# shield.net
KiCad netlist of a schematic drawn in EAGLE
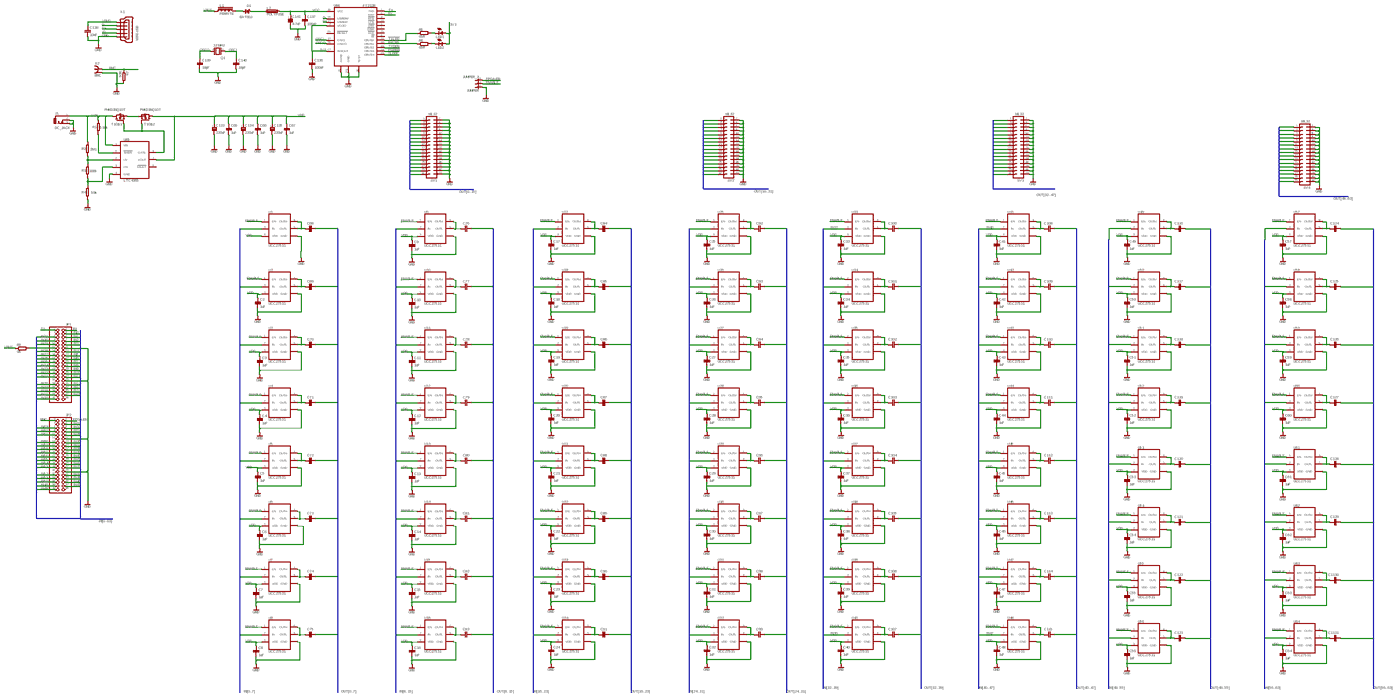
[diagram p0: schematic, sheet 1, overview]
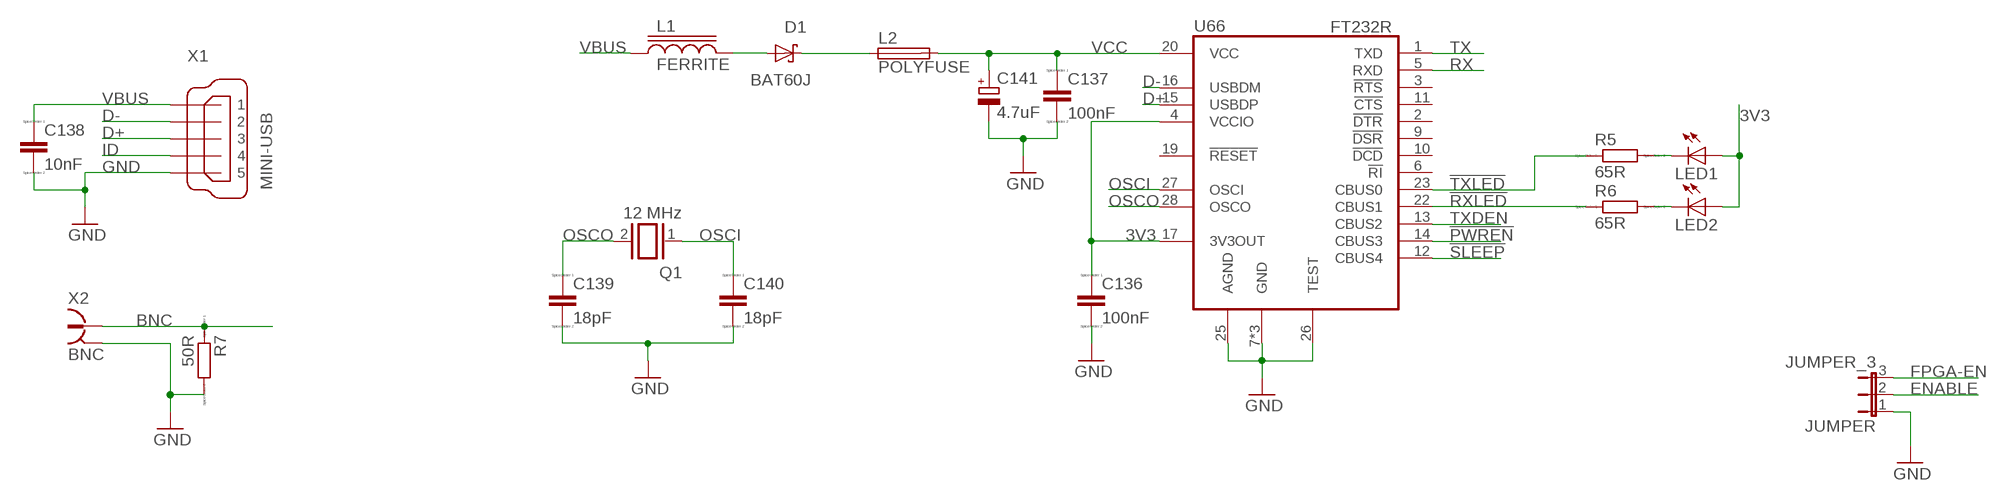
[diagram p1: schematic, sheet 1, part 1 of 4]
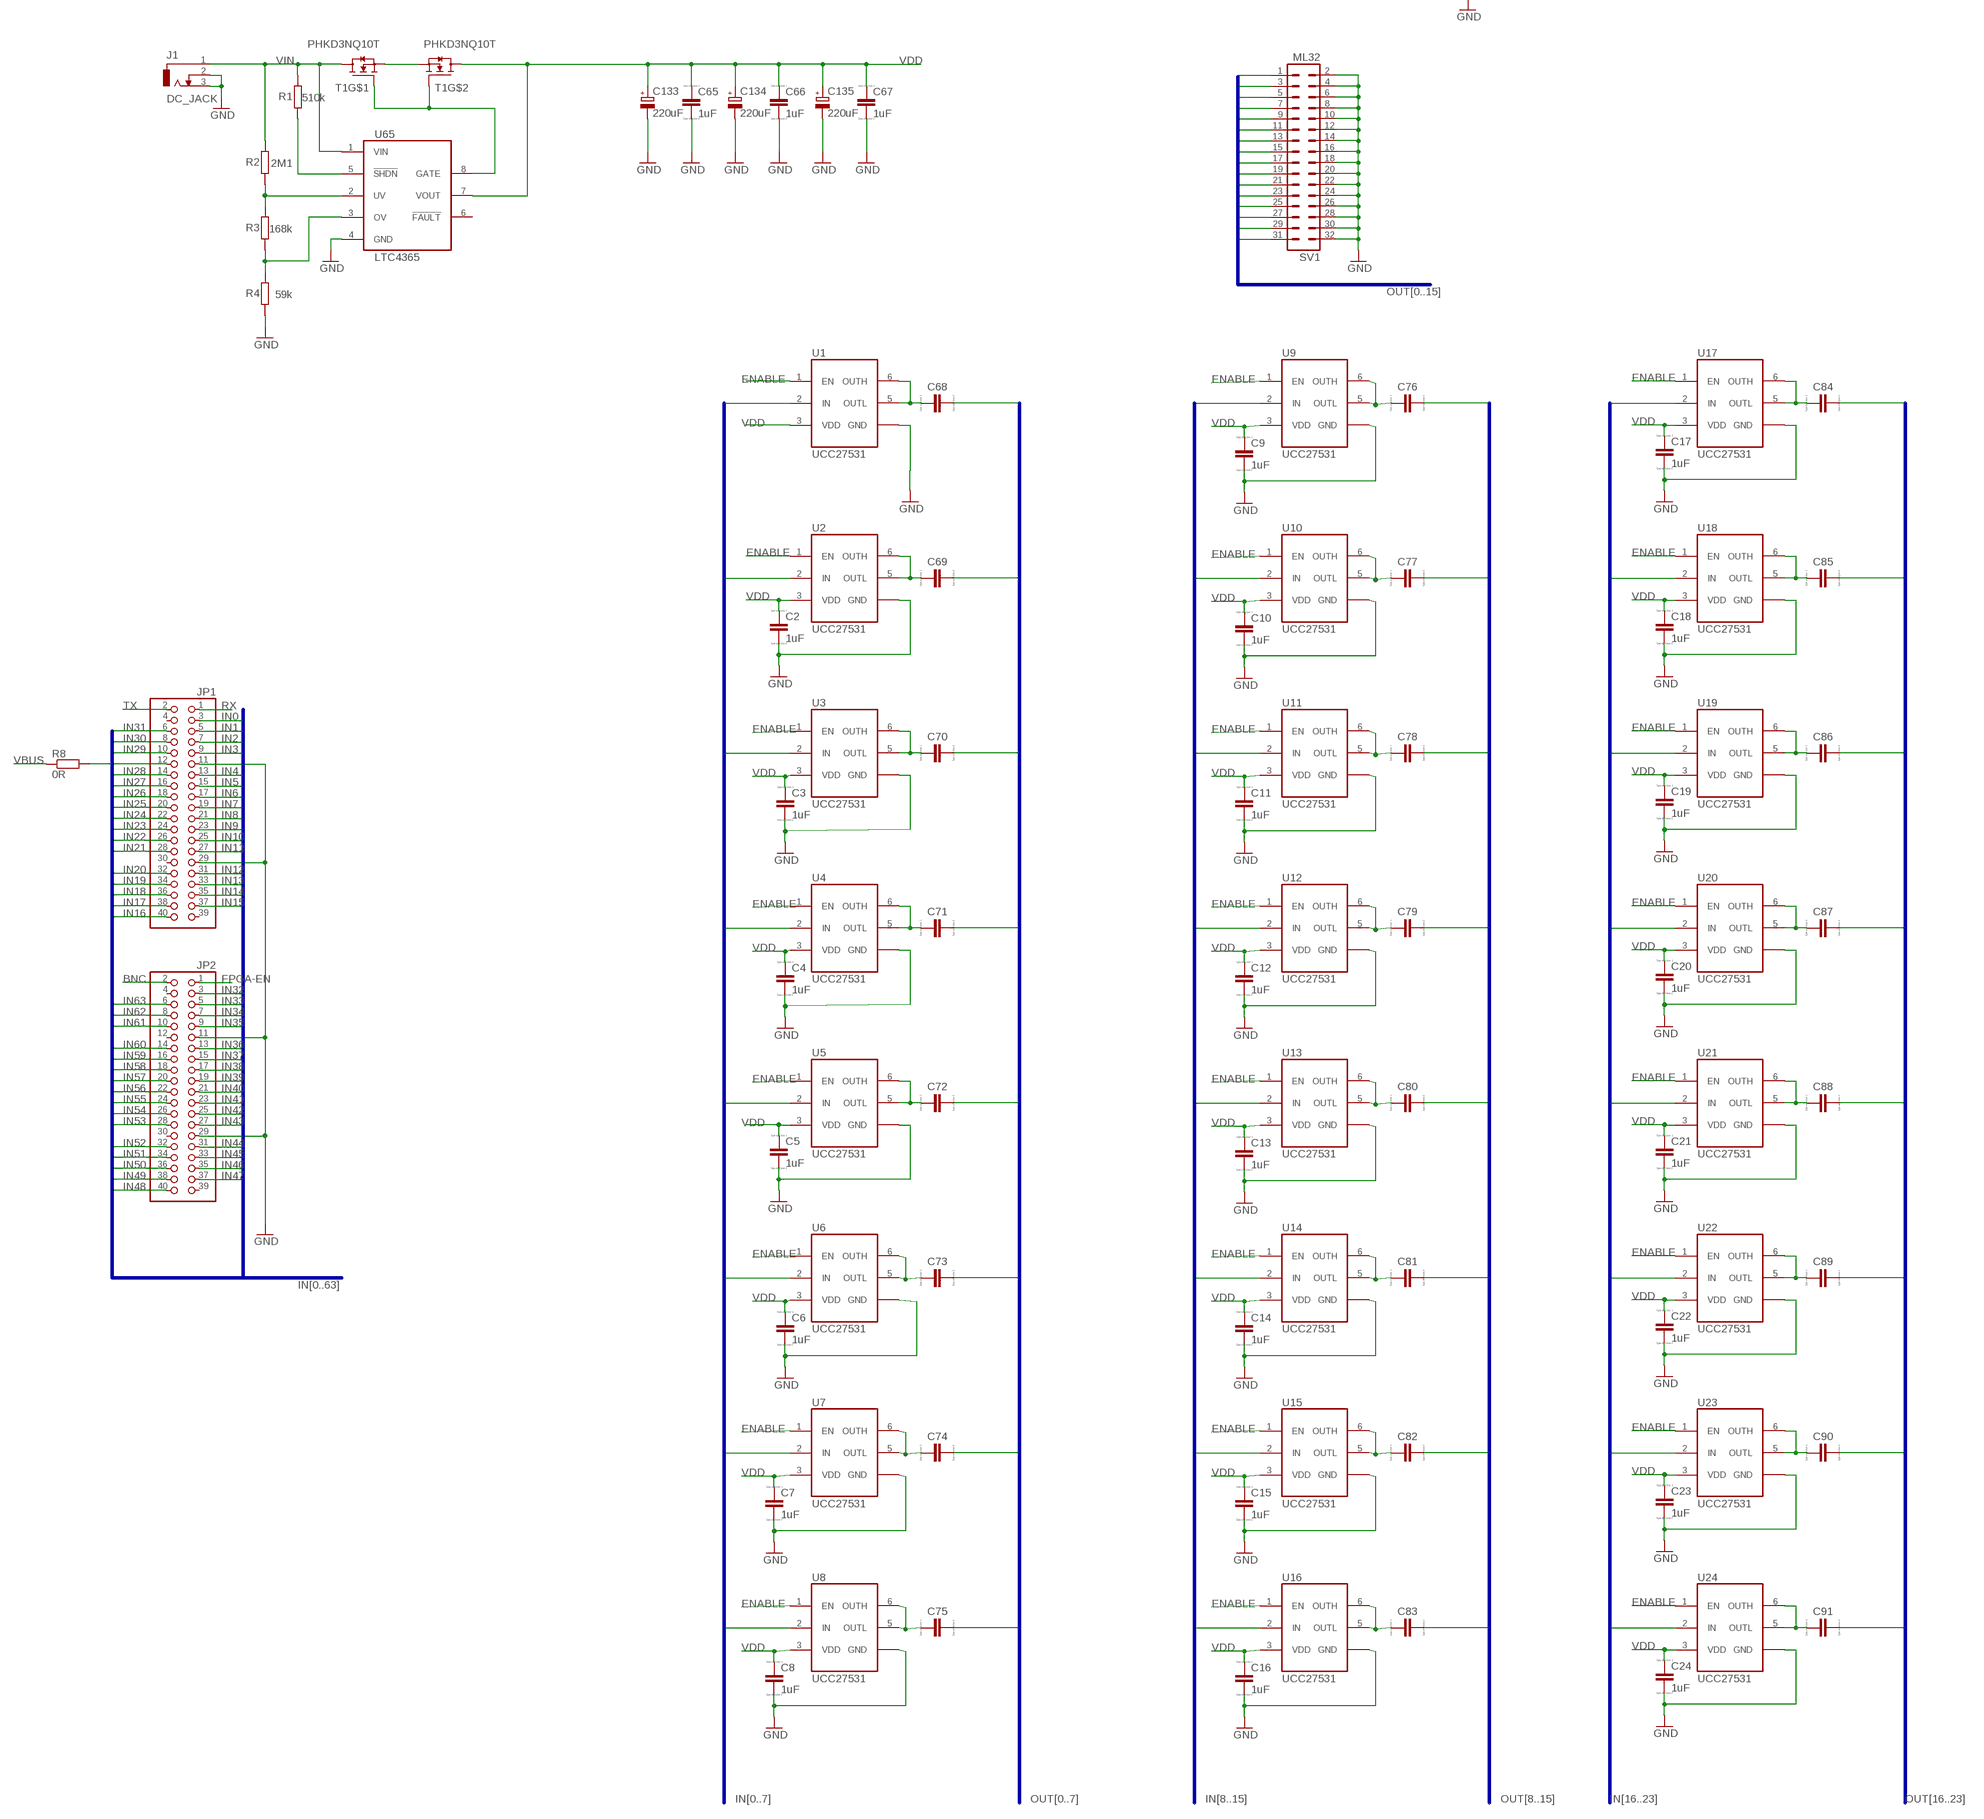
[diagram p2: schematic, sheet 1, part 2 of 4]
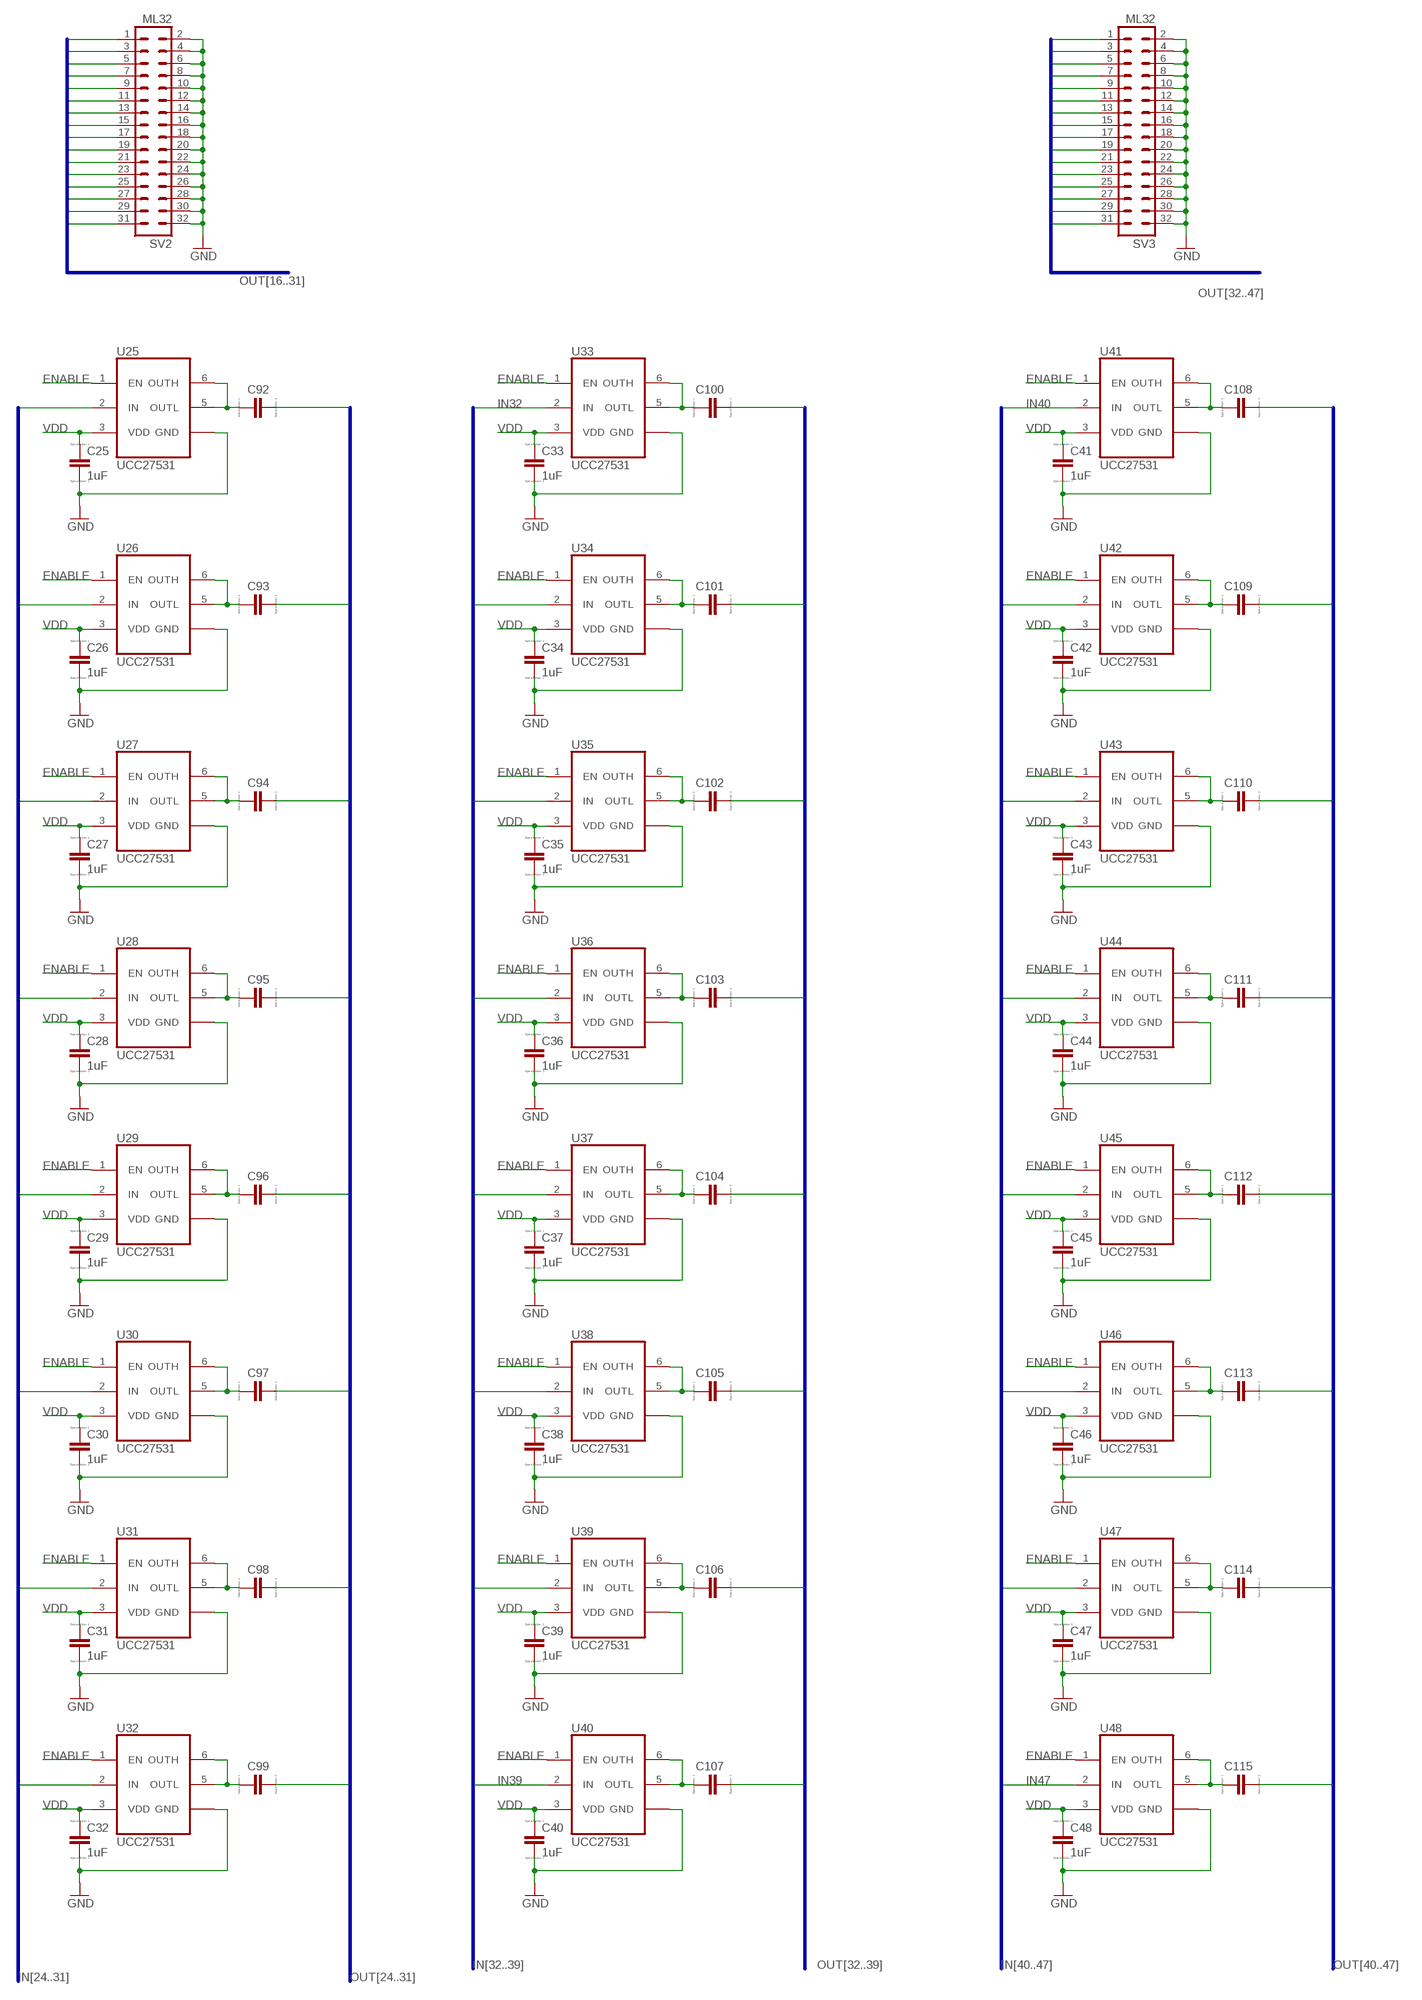
[diagram p3: schematic, sheet 1, part 3 of 4]
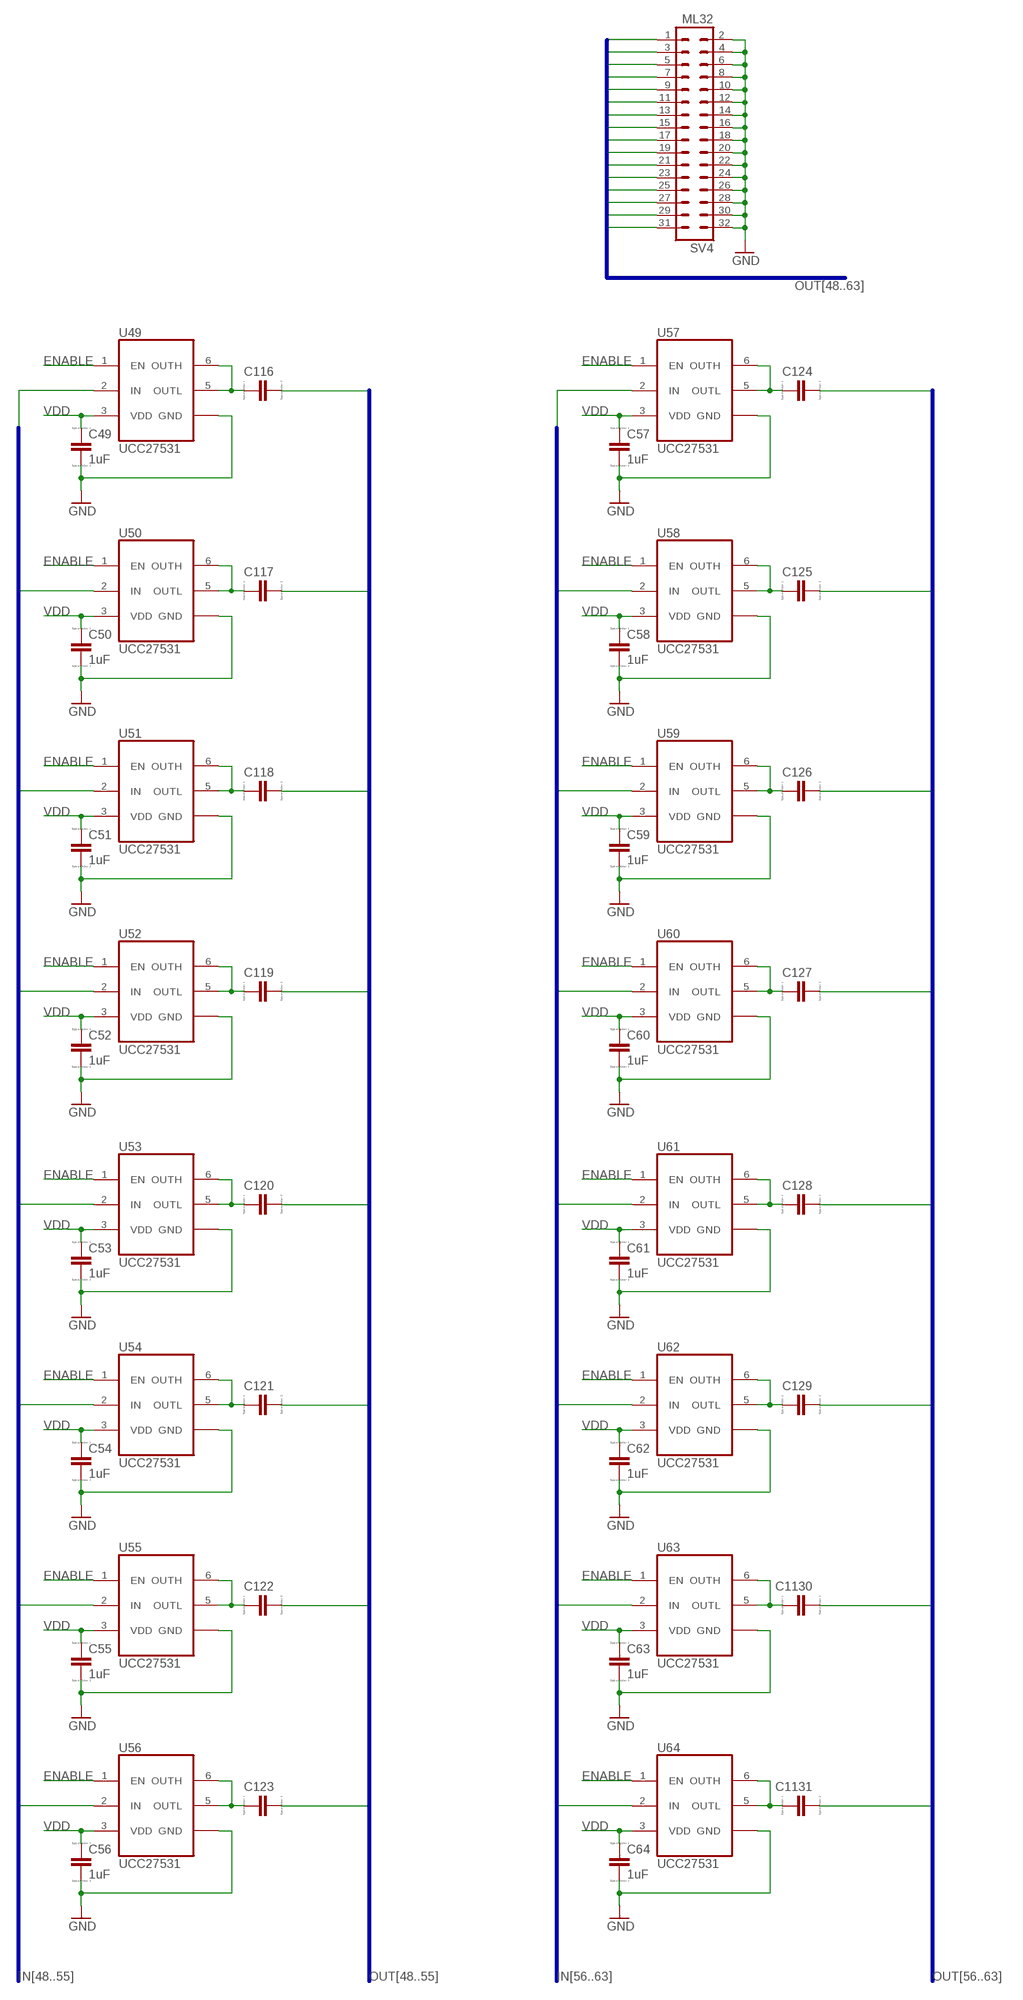
[diagram p4: schematic, sheet 1, part 4 of 4]

(export (version "E")
  (design (tool "Eeschema 10.0.6"))
  (components
    (comp (ref "C2")
      (value "1uF")
      (footprint "eagle-import:C0805")
      (libsource (lib "eagle-import") (part "C"))
    )
    (comp (ref "C3")
      (value "1uF")
      (footprint "eagle-import:C0805")
      (libsource (lib "eagle-import") (part "C"))
    )
    (comp (ref "C4")
      (value "1uF")
      (footprint "eagle-import:C0805")
      (libsource (lib "eagle-import") (part "C"))
    )
    (comp (ref "C5")
      (value "1uF")
      (footprint "eagle-import:C0805")
      (libsource (lib "eagle-import") (part "C"))
    )
    (comp (ref "C6")
      (value "1uF")
      (footprint "eagle-import:C0805")
      (libsource (lib "eagle-import") (part "C"))
    )
    (comp (ref "C7")
      (value "1uF")
      (footprint "eagle-import:C0805")
      (libsource (lib "eagle-import") (part "C"))
    )
    (comp (ref "C8")
      (value "1uF")
      (footprint "eagle-import:C0805")
      (libsource (lib "eagle-import") (part "C"))
    )
    (comp (ref "C9")
      (value "1uF")
      (footprint "eagle-import:C0805")
      (libsource (lib "eagle-import") (part "C"))
    )
    (comp (ref "C10")
      (value "1uF")
      (footprint "eagle-import:C0805")
      (libsource (lib "eagle-import") (part "C"))
    )
    (comp (ref "C11")
      (value "1uF")
      (footprint "eagle-import:C0805")
      (libsource (lib "eagle-import") (part "C"))
    )
    (comp (ref "C12")
      (value "1uF")
      (footprint "eagle-import:C0805")
      (libsource (lib "eagle-import") (part "C"))
    )
    (comp (ref "C13")
      (value "1uF")
      (footprint "eagle-import:C0805")
      (libsource (lib "eagle-import") (part "C"))
    )
    (comp (ref "C14")
      (value "1uF")
      (footprint "eagle-import:C0805")
      (libsource (lib "eagle-import") (part "C"))
    )
    (comp (ref "C15")
      (value "1uF")
      (footprint "eagle-import:C0805")
      (libsource (lib "eagle-import") (part "C"))
    )
    (comp (ref "C16")
      (value "1uF")
      (footprint "eagle-import:C0805")
      (libsource (lib "eagle-import") (part "C"))
    )
    (comp (ref "C17")
      (value "1uF")
      (footprint "eagle-import:C0805")
      (libsource (lib "eagle-import") (part "C"))
    )
    (comp (ref "C18")
      (value "1uF")
      (footprint "eagle-import:C0805")
      (libsource (lib "eagle-import") (part "C"))
    )
    (comp (ref "C19")
      (value "1uF")
      (footprint "eagle-import:C0805")
      (libsource (lib "eagle-import") (part "C"))
    )
    (comp (ref "C20")
      (value "1uF")
      (footprint "eagle-import:C0805")
      (libsource (lib "eagle-import") (part "C"))
    )
    (comp (ref "C21")
      (value "1uF")
      (footprint "eagle-import:C0805")
      (libsource (lib "eagle-import") (part "C"))
    )
    (comp (ref "C22")
      (value "1uF")
      (footprint "eagle-import:C0805")
      (libsource (lib "eagle-import") (part "C"))
    )
    (comp (ref "C23")
      (value "1uF")
      (footprint "eagle-import:C0805")
      (libsource (lib "eagle-import") (part "C"))
    )
    (comp (ref "C24")
      (value "1uF")
      (footprint "eagle-import:C0805")
      (libsource (lib "eagle-import") (part "C"))
    )
    (comp (ref "C25")
      (value "1uF")
      (footprint "eagle-import:C0805")
      (libsource (lib "eagle-import") (part "C"))
    )
    (comp (ref "C26")
      (value "1uF")
      (footprint "eagle-import:C0805")
      (libsource (lib "eagle-import") (part "C"))
    )
    (comp (ref "C27")
      (value "1uF")
      (footprint "eagle-import:C0805")
      (libsource (lib "eagle-import") (part "C"))
    )
    (comp (ref "C28")
      (value "1uF")
      (footprint "eagle-import:C0805")
      (libsource (lib "eagle-import") (part "C"))
    )
    (comp (ref "C29")
      (value "1uF")
      (footprint "eagle-import:C0805")
      (libsource (lib "eagle-import") (part "C"))
    )
    (comp (ref "C30")
      (value "1uF")
      (footprint "eagle-import:C0805")
      (libsource (lib "eagle-import") (part "C"))
    )
    (comp (ref "C31")
      (value "1uF")
      (footprint "eagle-import:C0805")
      (libsource (lib "eagle-import") (part "C"))
    )
    (comp (ref "C32")
      (value "1uF")
      (footprint "eagle-import:C0805")
      (libsource (lib "eagle-import") (part "C"))
    )
    (comp (ref "C33")
      (value "1uF")
      (footprint "eagle-import:C0805")
      (libsource (lib "eagle-import") (part "C"))
    )
    (comp (ref "C34")
      (value "1uF")
      (footprint "eagle-import:C0805")
      (libsource (lib "eagle-import") (part "C"))
    )
    (comp (ref "C35")
      (value "1uF")
      (footprint "eagle-import:C0805")
      (libsource (lib "eagle-import") (part "C"))
    )
    (comp (ref "C36")
      (value "1uF")
      (footprint "eagle-import:C0805")
      (libsource (lib "eagle-import") (part "C"))
    )
    (comp (ref "C37")
      (value "1uF")
      (footprint "eagle-import:C0805")
      (libsource (lib "eagle-import") (part "C"))
    )
    (comp (ref "C38")
      (value "1uF")
      (footprint "eagle-import:C0805")
      (libsource (lib "eagle-import") (part "C"))
    )
    (comp (ref "C39")
      (value "1uF")
      (footprint "eagle-import:C0805")
      (libsource (lib "eagle-import") (part "C"))
    )
    (comp (ref "C40")
      (value "1uF")
      (footprint "eagle-import:C0805")
      (libsource (lib "eagle-import") (part "C"))
    )
    (comp (ref "C41")
      (value "1uF")
      (footprint "eagle-import:C0805")
      (libsource (lib "eagle-import") (part "C"))
    )
    (comp (ref "C42")
      (value "1uF")
      (footprint "eagle-import:C0805")
      (libsource (lib "eagle-import") (part "C"))
    )
    (comp (ref "C43")
      (value "1uF")
      (footprint "eagle-import:C0805")
      (libsource (lib "eagle-import") (part "C"))
    )
    (comp (ref "C44")
      (value "1uF")
      (footprint "eagle-import:C0805")
      (libsource (lib "eagle-import") (part "C"))
    )
    (comp (ref "C45")
      (value "1uF")
      (footprint "eagle-import:C0805")
      (libsource (lib "eagle-import") (part "C"))
    )
    (comp (ref "C46")
      (value "1uF")
      (footprint "eagle-import:C0805")
      (libsource (lib "eagle-import") (part "C"))
    )
    (comp (ref "C47")
      (value "1uF")
      (footprint "eagle-import:C0805")
      (libsource (lib "eagle-import") (part "C"))
    )
    (comp (ref "C48")
      (value "1uF")
      (footprint "eagle-import:C0805")
      (libsource (lib "eagle-import") (part "C"))
    )
    (comp (ref "C49")
      (value "1uF")
      (footprint "eagle-import:C0805")
      (libsource (lib "eagle-import") (part "C"))
    )
    (comp (ref "C50")
      (value "1uF")
      (footprint "eagle-import:C0805")
      (libsource (lib "eagle-import") (part "C"))
    )
    (comp (ref "C51")
      (value "1uF")
      (footprint "eagle-import:C0805")
      (libsource (lib "eagle-import") (part "C"))
    )
    (comp (ref "C52")
      (value "1uF")
      (footprint "eagle-import:C0805")
      (libsource (lib "eagle-import") (part "C"))
    )
    (comp (ref "C53")
      (value "1uF")
      (footprint "eagle-import:C0805")
      (libsource (lib "eagle-import") (part "C"))
    )
    (comp (ref "C54")
      (value "1uF")
      (footprint "eagle-import:C0805")
      (libsource (lib "eagle-import") (part "C"))
    )
    (comp (ref "C55")
      (value "1uF")
      (footprint "eagle-import:C0805")
      (libsource (lib "eagle-import") (part "C"))
    )
    (comp (ref "C56")
      (value "1uF")
      (footprint "eagle-import:C0805")
      (libsource (lib "eagle-import") (part "C"))
    )
    (comp (ref "C57")
      (value "1uF")
      (footprint "eagle-import:C0805")
      (libsource (lib "eagle-import") (part "C"))
    )
    (comp (ref "C58")
      (value "1uF")
      (footprint "eagle-import:C0805")
      (libsource (lib "eagle-import") (part "C"))
    )
    (comp (ref "C59")
      (value "1uF")
      (footprint "eagle-import:C0805")
      (libsource (lib "eagle-import") (part "C"))
    )
    (comp (ref "C60")
      (value "1uF")
      (footprint "eagle-import:C0805")
      (libsource (lib "eagle-import") (part "C"))
    )
    (comp (ref "C61")
      (value "1uF")
      (footprint "eagle-import:C0805")
      (libsource (lib "eagle-import") (part "C"))
    )
    (comp (ref "C62")
      (value "1uF")
      (footprint "eagle-import:C0805")
      (libsource (lib "eagle-import") (part "C"))
    )
    (comp (ref "C63")
      (value "1uF")
      (footprint "eagle-import:C0805")
      (libsource (lib "eagle-import") (part "C"))
    )
    (comp (ref "C64")
      (value "1uF")
      (footprint "eagle-import:C0805")
      (libsource (lib "eagle-import") (part "C"))
    )
    (comp (ref "C65")
      (value "1uF")
      (footprint "eagle-import:C0805")
      (libsource (lib "eagle-import") (part "C"))
    )
    (comp (ref "C66")
      (value "1uF")
      (footprint "eagle-import:C0805")
      (libsource (lib "eagle-import") (part "C"))
    )
    (comp (ref "C67")
      (value "1uF")
      (footprint "eagle-import:C0805")
      (libsource (lib "eagle-import") (part "C"))
    )
    (comp (ref "C68")
      (value "C")
      (footprint "eagle-import:C0805")
      (libsource (lib "eagle-import") (part "C"))
    )
    (comp (ref "C69")
      (value "C")
      (footprint "eagle-import:C0805")
      (libsource (lib "eagle-import") (part "C"))
    )
    (comp (ref "C70")
      (value "C")
      (footprint "eagle-import:C0805")
      (libsource (lib "eagle-import") (part "C"))
    )
    (comp (ref "C71")
      (value "C")
      (footprint "eagle-import:C0805")
      (libsource (lib "eagle-import") (part "C"))
    )
    (comp (ref "C72")
      (value "C")
      (footprint "eagle-import:C0805")
      (libsource (lib "eagle-import") (part "C"))
    )
    (comp (ref "C73")
      (value "C")
      (footprint "eagle-import:C0805")
      (libsource (lib "eagle-import") (part "C"))
    )
    (comp (ref "C74")
      (value "C")
      (footprint "eagle-import:C0805")
      (libsource (lib "eagle-import") (part "C"))
    )
    (comp (ref "C75")
      (value "C")
      (footprint "eagle-import:C0805")
      (libsource (lib "eagle-import") (part "C"))
    )
    (comp (ref "C76")
      (value "C")
      (footprint "eagle-import:C0805")
      (libsource (lib "eagle-import") (part "C"))
    )
    (comp (ref "C77")
      (value "C")
      (footprint "eagle-import:C0805")
      (libsource (lib "eagle-import") (part "C"))
    )
    (comp (ref "C78")
      (value "C")
      (footprint "eagle-import:C0805")
      (libsource (lib "eagle-import") (part "C"))
    )
    (comp (ref "C79")
      (value "C")
      (footprint "eagle-import:C0805")
      (libsource (lib "eagle-import") (part "C"))
    )
    (comp (ref "C80")
      (value "C")
      (footprint "eagle-import:C0805")
      (libsource (lib "eagle-import") (part "C"))
    )
    (comp (ref "C81")
      (value "C")
      (footprint "eagle-import:C0805")
      (libsource (lib "eagle-import") (part "C"))
    )
    (comp (ref "C82")
      (value "C")
      (footprint "eagle-import:C0805")
      (libsource (lib "eagle-import") (part "C"))
    )
    (comp (ref "C83")
      (value "C")
      (footprint "eagle-import:C0805")
      (libsource (lib "eagle-import") (part "C"))
    )
    (comp (ref "C84")
      (value "C")
      (footprint "eagle-import:C0805")
      (libsource (lib "eagle-import") (part "C"))
    )
    (comp (ref "C85")
      (value "C")
      (footprint "eagle-import:C0805")
      (libsource (lib "eagle-import") (part "C"))
    )
    (comp (ref "C86")
      (value "C")
      (footprint "eagle-import:C0805")
      (libsource (lib "eagle-import") (part "C"))
    )
    (comp (ref "C87")
      (value "C")
      (footprint "eagle-import:C0805")
      (libsource (lib "eagle-import") (part "C"))
    )
    (comp (ref "C88")
      (value "C")
      (footprint "eagle-import:C0805")
      (libsource (lib "eagle-import") (part "C"))
    )
    (comp (ref "C89")
      (value "C")
      (footprint "eagle-import:C0805")
      (libsource (lib "eagle-import") (part "C"))
    )
    (comp (ref "C90")
      (value "C")
      (footprint "eagle-import:C0805")
      (libsource (lib "eagle-import") (part "C"))
    )
    (comp (ref "C91")
      (value "C")
      (footprint "eagle-import:C0805")
      (libsource (lib "eagle-import") (part "C"))
    )
    (comp (ref "C92")
      (value "C")
      (footprint "eagle-import:C0805")
      (libsource (lib "eagle-import") (part "C"))
    )
    (comp (ref "C93")
      (value "C")
      (footprint "eagle-import:C0805")
      (libsource (lib "eagle-import") (part "C"))
    )
    (comp (ref "C94")
      (value "C")
      (footprint "eagle-import:C0805")
      (libsource (lib "eagle-import") (part "C"))
    )
    (comp (ref "C95")
      (value "C")
      (footprint "eagle-import:C0805")
      (libsource (lib "eagle-import") (part "C"))
    )
    (comp (ref "C96")
      (value "C")
      (footprint "eagle-import:C0805")
      (libsource (lib "eagle-import") (part "C"))
    )
    (comp (ref "C97")
      (value "C")
      (footprint "eagle-import:C0805")
      (libsource (lib "eagle-import") (part "C"))
    )
    (comp (ref "C98")
      (value "C")
      (footprint "eagle-import:C0805")
      (libsource (lib "eagle-import") (part "C"))
    )
    (comp (ref "C99")
      (value "C")
      (footprint "eagle-import:C0805")
      (libsource (lib "eagle-import") (part "C"))
    )
    (comp (ref "C100")
      (value "C")
      (footprint "eagle-import:C0805")
      (libsource (lib "eagle-import") (part "C"))
    )
    (comp (ref "C101")
      (value "C")
      (footprint "eagle-import:C0805")
      (libsource (lib "eagle-import") (part "C"))
    )
    (comp (ref "C102")
      (value "C")
      (footprint "eagle-import:C0805")
      (libsource (lib "eagle-import") (part "C"))
    )
    (comp (ref "C103")
      (value "C")
      (footprint "eagle-import:C0805")
      (libsource (lib "eagle-import") (part "C"))
    )
    (comp (ref "C104")
      (value "C")
      (footprint "eagle-import:C0805")
      (libsource (lib "eagle-import") (part "C"))
    )
    (comp (ref "C105")
      (value "C")
      (footprint "eagle-import:C0805")
      (libsource (lib "eagle-import") (part "C"))
    )
    (comp (ref "C106")
      (value "C")
      (footprint "eagle-import:C0805")
      (libsource (lib "eagle-import") (part "C"))
    )
    (comp (ref "C107")
      (value "C")
      (footprint "eagle-import:C0805")
      (libsource (lib "eagle-import") (part "C"))
    )
    (comp (ref "C108")
      (value "C")
      (footprint "eagle-import:C0805")
      (libsource (lib "eagle-import") (part "C"))
    )
    (comp (ref "C109")
      (value "C")
      (footprint "eagle-import:C0805")
      (libsource (lib "eagle-import") (part "C"))
    )
    (comp (ref "C110")
      (value "C")
      (footprint "eagle-import:C0805")
      (libsource (lib "eagle-import") (part "C"))
    )
    (comp (ref "C111")
      (value "C")
      (footprint "eagle-import:C0805")
      (libsource (lib "eagle-import") (part "C"))
    )
    (comp (ref "C112")
      (value "C")
      (footprint "eagle-import:C0805")
      (libsource (lib "eagle-import") (part "C"))
    )
    (comp (ref "C113")
      (value "C")
      (footprint "eagle-import:C0805")
      (libsource (lib "eagle-import") (part "C"))
    )
    (comp (ref "C114")
      (value "C")
      (footprint "eagle-import:C0805")
      (libsource (lib "eagle-import") (part "C"))
    )
    (comp (ref "C115")
      (value "C")
      (footprint "eagle-import:C0805")
      (libsource (lib "eagle-import") (part "C"))
    )
    (comp (ref "C116")
      (value "C")
      (footprint "eagle-import:C0805")
      (libsource (lib "eagle-import") (part "C"))
    )
    (comp (ref "C117")
      (value "C")
      (footprint "eagle-import:C0805")
      (libsource (lib "eagle-import") (part "C"))
    )
    (comp (ref "C118")
      (value "C")
      (footprint "eagle-import:C0805")
      (libsource (lib "eagle-import") (part "C"))
    )
    (comp (ref "C119")
      (value "C")
      (footprint "eagle-import:C0805")
      (libsource (lib "eagle-import") (part "C"))
    )
    (comp (ref "C120")
      (value "C")
      (footprint "eagle-import:C0805")
      (libsource (lib "eagle-import") (part "C"))
    )
    (comp (ref "C121")
      (value "C")
      (footprint "eagle-import:C0805")
      (libsource (lib "eagle-import") (part "C"))
    )
    (comp (ref "C122")
      (value "C")
      (footprint "eagle-import:C0805")
      (libsource (lib "eagle-import") (part "C"))
    )
    (comp (ref "C123")
      (value "C")
      (footprint "eagle-import:C0805")
      (libsource (lib "eagle-import") (part "C"))
    )
    (comp (ref "C124")
      (value "C")
      (footprint "eagle-import:C0805")
      (libsource (lib "eagle-import") (part "C"))
    )
    (comp (ref "C125")
      (value "C")
      (footprint "eagle-import:C0805")
      (libsource (lib "eagle-import") (part "C"))
    )
    (comp (ref "C126")
      (value "C")
      (footprint "eagle-import:C0805")
      (libsource (lib "eagle-import") (part "C"))
    )
    (comp (ref "C127")
      (value "C")
      (footprint "eagle-import:C0805")
      (libsource (lib "eagle-import") (part "C"))
    )
    (comp (ref "C128")
      (value "C")
      (footprint "eagle-import:C0805")
      (libsource (lib "eagle-import") (part "C"))
    )
    (comp (ref "C129")
      (value "C")
      (footprint "eagle-import:C0805")
      (libsource (lib "eagle-import") (part "C"))
    )
    (comp (ref "C133")
      (value "220uF")
      (footprint "eagle-import:E5-10,5")
      (libsource (lib "eagle-import") (part "CPOL-EUE5-10.5"))
    )
    (comp (ref "C134")
      (value "220uF")
      (footprint "eagle-import:E5-10,5")
      (libsource (lib "eagle-import") (part "CPOL-EUE5-10.5"))
    )
    (comp (ref "C135")
      (value "220uF")
      (footprint "eagle-import:E5-10,5")
      (libsource (lib "eagle-import") (part "CPOL-EUE5-10.5"))
    )
    (comp (ref "C136")
      (value "100nF")
      (footprint "eagle-import:C0805")
      (libsource (lib "eagle-import") (part "C"))
    )
    (comp (ref "C137")
      (value "100nF")
      (footprint "eagle-import:C0805")
      (libsource (lib "eagle-import") (part "C"))
    )
    (comp (ref "C138")
      (value "10nF")
      (footprint "eagle-import:C0805")
      (libsource (lib "eagle-import") (part "C"))
    )
    (comp (ref "C139")
      (value "18pF")
      (footprint "eagle-import:C0603")
      (libsource (lib "eagle-import") (part "CC0603"))
    )
    (comp (ref "C140")
      (value "18pF")
      (footprint "eagle-import:C0603")
      (libsource (lib "eagle-import") (part "CC0603"))
    )
    (comp (ref "C141")
      (value "4.7uF")
      (footprint "eagle-import:E2-5")
      (libsource (lib "eagle-import") (part "CPOL-EUE2-5"))
    )
    (comp (ref "C1130")
      (value "C")
      (footprint "eagle-import:C0805")
      (libsource (lib "eagle-import") (part "C"))
    )
    (comp (ref "C1131")
      (value "C")
      (footprint "eagle-import:C0805")
      (libsource (lib "eagle-import") (part "C"))
    )
    (comp (ref "D1")
      (value "BAT60J")
      (footprint "eagle-import:SOD323_ST")
      (libsource (lib "eagle-import") (part "BAT60J"))
    )
    (comp (ref "J1")
      (value "DC_JACK")
      (footprint "eagle-import:DCJ0202")
      (libsource (lib "eagle-import") (part "DC_JACK"))
    )
    (comp (ref "JP1")
      (value "PINHD-2X20")
      (footprint "eagle-import:2X20")
      (libsource (lib "eagle-import") (part "PINHD-2X20"))
    )
    (comp (ref "JP2")
      (value "PINHD-2X20")
      (footprint "eagle-import:2X20")
      (libsource (lib "eagle-import") (part "PINHD-2X20"))
    )
    (comp (ref "JUMPER")
      (value "JUMPER_3")
      (footprint "eagle-import:JP2")
      (libsource (lib "eagle-import") (part "JUMPER_3"))
    )
    (comp (ref "L1")
      (value "FERRITE")
      (footprint "eagle-import:SML0805")
      (libsource (lib "eagle-import") (part "FERRITE"))
    )
    (comp (ref "L2")
      (value "POLYFUSE")
      (footprint "eagle-import:SML0805")
      (libsource (lib "eagle-import") (part "POLYFUSE"))
    )
    (comp (ref "LED1")
      (value "LEDSML1206")
      (footprint "eagle-import:SML1206")
      (libsource (lib "eagle-import") (part "LEDSML1206"))
    )
    (comp (ref "LED2")
      (value "LEDSML1206")
      (footprint "eagle-import:SML1206")
      (libsource (lib "eagle-import") (part "LEDSML1206"))
    )
    (comp (ref "Q1")
      (value "12 MHz")
      (footprint "eagle-import:QS")
      (libsource (lib "eagle-import") (part "XTAL/S"))
    )
    (comp (ref "R1")
      (value "510k")
      (footprint "eagle-import:R0805")
      (libsource (lib "eagle-import") (part "resistor_348_R-EU_R0805"))
    )
    (comp (ref "R2")
      (value "2M1")
      (footprint "eagle-import:R0805")
      (libsource (lib "eagle-import") (part "resistor_348_R-EU_R0805"))
    )
    (comp (ref "R3")
      (value "168k")
      (footprint "eagle-import:R0805")
      (libsource (lib "eagle-import") (part "resistor_348_R-EU_R0805"))
    )
    (comp (ref "R4")
      (value "59k")
      (footprint "eagle-import:R0805")
      (libsource (lib "eagle-import") (part "resistor_348_R-EU_R0805"))
    )
    (comp (ref "R5")
      (value "65R")
      (footprint "eagle-import:R0805")
      (libsource (lib "eagle-import") (part "R"))
    )
    (comp (ref "R6")
      (value "65R")
      (footprint "eagle-import:R0805")
      (libsource (lib "eagle-import") (part "R"))
    )
    (comp (ref "R7")
      (value "50R")
      (footprint "eagle-import:R0603")
      (libsource (lib "eagle-import") (part "RR0603"))
    )
    (comp (ref "R8")
      (value "0R")
      (footprint "eagle-import:R0805")
      (libsource (lib "eagle-import") (part "R-EU_R0805"))
    )
    (comp (ref "SV1")
      (value "ML32")
      (footprint "eagle-import:ML32")
      (libsource (lib "eagle-import") (part "ML32"))
    )
    (comp (ref "SV2")
      (value "ML32")
      (footprint "eagle-import:ML32")
      (libsource (lib "eagle-import") (part "ML32"))
    )
    (comp (ref "SV3")
      (value "ML32")
      (footprint "eagle-import:ML32")
      (libsource (lib "eagle-import") (part "ML32"))
    )
    (comp (ref "SV4")
      (value "ML32")
      (footprint "eagle-import:ML32")
      (libsource (lib "eagle-import") (part "ML32"))
    )
    (comp (ref "T1")
      (value "PHKD3NQ10T")
      (footprint "eagle-import:SO8")
      (libsource (lib "eagle-import") (part "PHKD3NQ10T"))
    )
    (comp (ref "U1")
      (value "UCC27531")
      (footprint "eagle-import:DBV_R-PDSO-G6")
      (libsource (lib "eagle-import") (part "UCC27531"))
    )
    (comp (ref "U2")
      (value "UCC27531")
      (footprint "eagle-import:DBV_R-PDSO-G6")
      (libsource (lib "eagle-import") (part "UCC27531"))
    )
    (comp (ref "U3")
      (value "UCC27531")
      (footprint "eagle-import:DBV_R-PDSO-G6")
      (libsource (lib "eagle-import") (part "UCC27531"))
    )
    (comp (ref "U4")
      (value "UCC27531")
      (footprint "eagle-import:DBV_R-PDSO-G6")
      (libsource (lib "eagle-import") (part "UCC27531"))
    )
    (comp (ref "U5")
      (value "UCC27531")
      (footprint "eagle-import:DBV_R-PDSO-G6")
      (libsource (lib "eagle-import") (part "UCC27531"))
    )
    (comp (ref "U6")
      (value "UCC27531")
      (footprint "eagle-import:DBV_R-PDSO-G6")
      (libsource (lib "eagle-import") (part "UCC27531"))
    )
    (comp (ref "U7")
      (value "UCC27531")
      (footprint "eagle-import:DBV_R-PDSO-G6")
      (libsource (lib "eagle-import") (part "UCC27531"))
    )
    (comp (ref "U8")
      (value "UCC27531")
      (footprint "eagle-import:DBV_R-PDSO-G6")
      (libsource (lib "eagle-import") (part "UCC27531"))
    )
    (comp (ref "U9")
      (value "UCC27531")
      (footprint "eagle-import:DBV_R-PDSO-G6")
      (libsource (lib "eagle-import") (part "UCC27531"))
    )
    (comp (ref "U10")
      (value "UCC27531")
      (footprint "eagle-import:DBV_R-PDSO-G6")
      (libsource (lib "eagle-import") (part "UCC27531"))
    )
    (comp (ref "U11")
      (value "UCC27531")
      (footprint "eagle-import:DBV_R-PDSO-G6")
      (libsource (lib "eagle-import") (part "UCC27531"))
    )
    (comp (ref "U12")
      (value "UCC27531")
      (footprint "eagle-import:DBV_R-PDSO-G6")
      (libsource (lib "eagle-import") (part "UCC27531"))
    )
    (comp (ref "U13")
      (value "UCC27531")
      (footprint "eagle-import:DBV_R-PDSO-G6")
      (libsource (lib "eagle-import") (part "UCC27531"))
    )
    (comp (ref "U14")
      (value "UCC27531")
      (footprint "eagle-import:DBV_R-PDSO-G6")
      (libsource (lib "eagle-import") (part "UCC27531"))
    )
    (comp (ref "U15")
      (value "UCC27531")
      (footprint "eagle-import:DBV_R-PDSO-G6")
      (libsource (lib "eagle-import") (part "UCC27531"))
    )
    (comp (ref "U16")
      (value "UCC27531")
      (footprint "eagle-import:DBV_R-PDSO-G6")
      (libsource (lib "eagle-import") (part "UCC27531"))
    )
    (comp (ref "U17")
      (value "UCC27531")
      (footprint "eagle-import:DBV_R-PDSO-G6")
      (libsource (lib "eagle-import") (part "UCC27531"))
    )
    (comp (ref "U18")
      (value "UCC27531")
      (footprint "eagle-import:DBV_R-PDSO-G6")
      (libsource (lib "eagle-import") (part "UCC27531"))
    )
    (comp (ref "U19")
      (value "UCC27531")
      (footprint "eagle-import:DBV_R-PDSO-G6")
      (libsource (lib "eagle-import") (part "UCC27531"))
    )
    (comp (ref "U20")
      (value "UCC27531")
      (footprint "eagle-import:DBV_R-PDSO-G6")
      (libsource (lib "eagle-import") (part "UCC27531"))
    )
    (comp (ref "U21")
      (value "UCC27531")
      (footprint "eagle-import:DBV_R-PDSO-G6")
      (libsource (lib "eagle-import") (part "UCC27531"))
    )
    (comp (ref "U22")
      (value "UCC27531")
      (footprint "eagle-import:DBV_R-PDSO-G6")
      (libsource (lib "eagle-import") (part "UCC27531"))
    )
    (comp (ref "U23")
      (value "UCC27531")
      (footprint "eagle-import:DBV_R-PDSO-G6")
      (libsource (lib "eagle-import") (part "UCC27531"))
    )
    (comp (ref "U24")
      (value "UCC27531")
      (footprint "eagle-import:DBV_R-PDSO-G6")
      (libsource (lib "eagle-import") (part "UCC27531"))
    )
    (comp (ref "U25")
      (value "UCC27531")
      (footprint "eagle-import:DBV_R-PDSO-G6")
      (libsource (lib "eagle-import") (part "UCC27531"))
    )
    (comp (ref "U26")
      (value "UCC27531")
      (footprint "eagle-import:DBV_R-PDSO-G6")
      (libsource (lib "eagle-import") (part "UCC27531"))
    )
    (comp (ref "U27")
      (value "UCC27531")
      (footprint "eagle-import:DBV_R-PDSO-G6")
      (libsource (lib "eagle-import") (part "UCC27531"))
    )
    (comp (ref "U28")
      (value "UCC27531")
      (footprint "eagle-import:DBV_R-PDSO-G6")
      (libsource (lib "eagle-import") (part "UCC27531"))
    )
    (comp (ref "U29")
      (value "UCC27531")
      (footprint "eagle-import:DBV_R-PDSO-G6")
      (libsource (lib "eagle-import") (part "UCC27531"))
    )
    (comp (ref "U30")
      (value "UCC27531")
      (footprint "eagle-import:DBV_R-PDSO-G6")
      (libsource (lib "eagle-import") (part "UCC27531"))
    )
    (comp (ref "U31")
      (value "UCC27531")
      (footprint "eagle-import:DBV_R-PDSO-G6")
      (libsource (lib "eagle-import") (part "UCC27531"))
    )
    (comp (ref "U32")
      (value "UCC27531")
      (footprint "eagle-import:DBV_R-PDSO-G6")
      (libsource (lib "eagle-import") (part "UCC27531"))
    )
    (comp (ref "U33")
      (value "UCC27531")
      (footprint "eagle-import:DBV_R-PDSO-G6")
      (libsource (lib "eagle-import") (part "UCC27531"))
    )
    (comp (ref "U34")
      (value "UCC27531")
      (footprint "eagle-import:DBV_R-PDSO-G6")
      (libsource (lib "eagle-import") (part "UCC27531"))
    )
    (comp (ref "U35")
      (value "UCC27531")
      (footprint "eagle-import:DBV_R-PDSO-G6")
      (libsource (lib "eagle-import") (part "UCC27531"))
    )
    (comp (ref "U36")
      (value "UCC27531")
      (footprint "eagle-import:DBV_R-PDSO-G6")
      (libsource (lib "eagle-import") (part "UCC27531"))
    )
    (comp (ref "U37")
      (value "UCC27531")
      (footprint "eagle-import:DBV_R-PDSO-G6")
      (libsource (lib "eagle-import") (part "UCC27531"))
    )
    (comp (ref "U38")
      (value "UCC27531")
      (footprint "eagle-import:DBV_R-PDSO-G6")
      (libsource (lib "eagle-import") (part "UCC27531"))
    )
    (comp (ref "U39")
      (value "UCC27531")
      (footprint "eagle-import:DBV_R-PDSO-G6")
      (libsource (lib "eagle-import") (part "UCC27531"))
    )
    (comp (ref "U40")
      (value "UCC27531")
      (footprint "eagle-import:DBV_R-PDSO-G6")
      (libsource (lib "eagle-import") (part "UCC27531"))
    )
    (comp (ref "U41")
      (value "UCC27531")
      (footprint "eagle-import:DBV_R-PDSO-G6")
      (libsource (lib "eagle-import") (part "UCC27531"))
    )
    (comp (ref "U42")
      (value "UCC27531")
      (footprint "eagle-import:DBV_R-PDSO-G6")
      (libsource (lib "eagle-import") (part "UCC27531"))
    )
    (comp (ref "U43")
      (value "UCC27531")
      (footprint "eagle-import:DBV_R-PDSO-G6")
      (libsource (lib "eagle-import") (part "UCC27531"))
    )
    (comp (ref "U44")
      (value "UCC27531")
      (footprint "eagle-import:DBV_R-PDSO-G6")
      (libsource (lib "eagle-import") (part "UCC27531"))
    )
    (comp (ref "U45")
      (value "UCC27531")
      (footprint "eagle-import:DBV_R-PDSO-G6")
      (libsource (lib "eagle-import") (part "UCC27531"))
    )
    (comp (ref "U46")
      (value "UCC27531")
      (footprint "eagle-import:DBV_R-PDSO-G6")
      (libsource (lib "eagle-import") (part "UCC27531"))
    )
    (comp (ref "U47")
      (value "UCC27531")
      (footprint "eagle-import:DBV_R-PDSO-G6")
      (libsource (lib "eagle-import") (part "UCC27531"))
    )
    (comp (ref "U48")
      (value "UCC27531")
      (footprint "eagle-import:DBV_R-PDSO-G6")
      (libsource (lib "eagle-import") (part "UCC27531"))
    )
    (comp (ref "U49")
      (value "UCC27531")
      (footprint "eagle-import:DBV_R-PDSO-G6")
      (libsource (lib "eagle-import") (part "UCC27531"))
    )
    (comp (ref "U50")
      (value "UCC27531")
      (footprint "eagle-import:DBV_R-PDSO-G6")
      (libsource (lib "eagle-import") (part "UCC27531"))
    )
    (comp (ref "U51")
      (value "UCC27531")
      (footprint "eagle-import:DBV_R-PDSO-G6")
      (libsource (lib "eagle-import") (part "UCC27531"))
    )
    (comp (ref "U52")
      (value "UCC27531")
      (footprint "eagle-import:DBV_R-PDSO-G6")
      (libsource (lib "eagle-import") (part "UCC27531"))
    )
    (comp (ref "U53")
      (value "UCC27531")
      (footprint "eagle-import:DBV_R-PDSO-G6")
      (libsource (lib "eagle-import") (part "UCC27531"))
    )
    (comp (ref "U54")
      (value "UCC27531")
      (footprint "eagle-import:DBV_R-PDSO-G6")
      (libsource (lib "eagle-import") (part "UCC27531"))
    )
    (comp (ref "U55")
      (value "UCC27531")
      (footprint "eagle-import:DBV_R-PDSO-G6")
      (libsource (lib "eagle-import") (part "UCC27531"))
    )
    (comp (ref "U56")
      (value "UCC27531")
      (footprint "eagle-import:DBV_R-PDSO-G6")
      (libsource (lib "eagle-import") (part "UCC27531"))
    )
    (comp (ref "U57")
      (value "UCC27531")
      (footprint "eagle-import:DBV_R-PDSO-G6")
      (libsource (lib "eagle-import") (part "UCC27531"))
    )
    (comp (ref "U58")
      (value "UCC27531")
      (footprint "eagle-import:DBV_R-PDSO-G6")
      (libsource (lib "eagle-import") (part "UCC27531"))
    )
    (comp (ref "U59")
      (value "UCC27531")
      (footprint "eagle-import:DBV_R-PDSO-G6")
      (libsource (lib "eagle-import") (part "UCC27531"))
    )
    (comp (ref "U60")
      (value "UCC27531")
      (footprint "eagle-import:DBV_R-PDSO-G6")
      (libsource (lib "eagle-import") (part "UCC27531"))
    )
    (comp (ref "U61")
      (value "UCC27531")
      (footprint "eagle-import:DBV_R-PDSO-G6")
      (libsource (lib "eagle-import") (part "UCC27531"))
    )
    (comp (ref "U62")
      (value "UCC27531")
      (footprint "eagle-import:DBV_R-PDSO-G6")
      (libsource (lib "eagle-import") (part "UCC27531"))
    )
    (comp (ref "U63")
      (value "UCC27531")
      (footprint "eagle-import:DBV_R-PDSO-G6")
      (libsource (lib "eagle-import") (part "UCC27531"))
    )
    (comp (ref "U64")
      (value "UCC27531")
      (footprint "eagle-import:DBV_R-PDSO-G6")
      (libsource (lib "eagle-import") (part "UCC27531"))
    )
    (comp (ref "U65")
      (value "LTC4365")
      (footprint "eagle-import:TSOT23-8")
      (libsource (lib "eagle-import") (part "LTC4365"))
    )
    (comp (ref "U66")
      (value "FT232R")
      (footprint "eagle-import:SSOP28")
      (libsource (lib "eagle-import") (part "FT232R"))
    )
    (comp (ref "X1")
      (value "MINI-USB")
      (footprint "eagle-import:32005-201")
      (libsource (lib "eagle-import") (part "MINI_USB"))
    )
    (comp (ref "X2")
      (value "BNC")
      (footprint "eagle-import:BNC_CUSTOM")
      (libsource (lib "eagle-import") (part "BNC"))
    )
  )
  (nets
    (net (code "1") (name "/3V3") (class "Default")
      (node (ref "C136") (pin "1") (pinfunction "1_1") (pintype "passive"))
      (node (ref "LED1") (pin "A") (pinfunction "A_A") (pintype "passive"))
      (node (ref "LED2") (pin "A") (pinfunction "A_A") (pintype "passive"))
      (node (ref "U66") (pin "17") (pinfunction "3V3OUT_17") (pintype "power_in"))
      (node (ref "U66") (pin "4") (pinfunction "VCCIO_4") (pintype "power_in"))
    )
    (net (code "2") (name "/BNC") (class "Default")
      (node (ref "JP2") (pin "2") (pinfunction "2_2") (pintype "passive"))
      (node (ref "R7") (pin "1") (pinfunction "1_1") (pintype "passive"))
      (node (ref "X2") (pin "1") (pinfunction "1_1") (pintype "passive"))
    )
    (net (code "3") (name "/D+") (class "Default")
      (node (ref "U66") (pin "15") (pinfunction "USBDP_15") (pintype "bidirectional"))
      (node (ref "X1") (pin "3") (pinfunction "3_3") (pintype "passive"))
    )
    (net (code "4") (name "/D-") (class "Default")
      (node (ref "U66") (pin "16") (pinfunction "USBDM_16") (pintype "bidirectional"))
      (node (ref "X1") (pin "2") (pinfunction "2_2") (pintype "passive"))
    )
    (net (code "5") (name "/ENABLE") (class "Default")
      (node (ref "JUMPER") (pin "2") (pinfunction "2_2") (pintype "passive"))
      (node (ref "U1") (pin "1") (pinfunction "EN_1") (pintype "input"))
      (node (ref "U10") (pin "1") (pinfunction "EN_1") (pintype "input"))
      (node (ref "U11") (pin "1") (pinfunction "EN_1") (pintype "input"))
      (node (ref "U12") (pin "1") (pinfunction "EN_1") (pintype "input"))
      (node (ref "U13") (pin "1") (pinfunction "EN_1") (pintype "input"))
      (node (ref "U14") (pin "1") (pinfunction "EN_1") (pintype "input"))
      (node (ref "U15") (pin "1") (pinfunction "EN_1") (pintype "input"))
      (node (ref "U16") (pin "1") (pinfunction "EN_1") (pintype "input"))
      (node (ref "U17") (pin "1") (pinfunction "EN_1") (pintype "input"))
      (node (ref "U18") (pin "1") (pinfunction "EN_1") (pintype "input"))
      (node (ref "U19") (pin "1") (pinfunction "EN_1") (pintype "input"))
      (node (ref "U2") (pin "1") (pinfunction "EN_1") (pintype "input"))
      (node (ref "U20") (pin "1") (pinfunction "EN_1") (pintype "input"))
      (node (ref "U21") (pin "1") (pinfunction "EN_1") (pintype "input"))
      (node (ref "U22") (pin "1") (pinfunction "EN_1") (pintype "input"))
      (node (ref "U23") (pin "1") (pinfunction "EN_1") (pintype "input"))
      (node (ref "U24") (pin "1") (pinfunction "EN_1") (pintype "input"))
      (node (ref "U25") (pin "1") (pinfunction "EN_1") (pintype "input"))
      (node (ref "U26") (pin "1") (pinfunction "EN_1") (pintype "input"))
      (node (ref "U27") (pin "1") (pinfunction "EN_1") (pintype "input"))
      (node (ref "U28") (pin "1") (pinfunction "EN_1") (pintype "input"))
      (node (ref "U29") (pin "1") (pinfunction "EN_1") (pintype "input"))
      (node (ref "U3") (pin "1") (pinfunction "EN_1") (pintype "input"))
      (node (ref "U30") (pin "1") (pinfunction "EN_1") (pintype "input"))
      (node (ref "U31") (pin "1") (pinfunction "EN_1") (pintype "input"))
      (node (ref "U32") (pin "1") (pinfunction "EN_1") (pintype "input"))
      (node (ref "U33") (pin "1") (pinfunction "EN_1") (pintype "input"))
      (node (ref "U34") (pin "1") (pinfunction "EN_1") (pintype "input"))
      (node (ref "U35") (pin "1") (pinfunction "EN_1") (pintype "input"))
      (node (ref "U36") (pin "1") (pinfunction "EN_1") (pintype "input"))
      (node (ref "U37") (pin "1") (pinfunction "EN_1") (pintype "input"))
      (node (ref "U38") (pin "1") (pinfunction "EN_1") (pintype "input"))
      (node (ref "U39") (pin "1") (pinfunction "EN_1") (pintype "input"))
      (node (ref "U4") (pin "1") (pinfunction "EN_1") (pintype "input"))
      (node (ref "U40") (pin "1") (pinfunction "EN_1") (pintype "input"))
      (node (ref "U41") (pin "1") (pinfunction "EN_1") (pintype "input"))
      (node (ref "U42") (pin "1") (pinfunction "EN_1") (pintype "input"))
      (node (ref "U43") (pin "1") (pinfunction "EN_1") (pintype "input"))
      (node (ref "U44") (pin "1") (pinfunction "EN_1") (pintype "input"))
      (node (ref "U45") (pin "1") (pinfunction "EN_1") (pintype "input"))
      (node (ref "U46") (pin "1") (pinfunction "EN_1") (pintype "input"))
      (node (ref "U47") (pin "1") (pinfunction "EN_1") (pintype "input"))
      (node (ref "U48") (pin "1") (pinfunction "EN_1") (pintype "input"))
      (node (ref "U49") (pin "1") (pinfunction "EN_1") (pintype "input"))
      (node (ref "U5") (pin "1") (pinfunction "EN_1") (pintype "input"))
      (node (ref "U50") (pin "1") (pinfunction "EN_1") (pintype "input"))
      (node (ref "U51") (pin "1") (pinfunction "EN_1") (pintype "input"))
      (node (ref "U52") (pin "1") (pinfunction "EN_1") (pintype "input"))
      (node (ref "U53") (pin "1") (pinfunction "EN_1") (pintype "input"))
      (node (ref "U54") (pin "1") (pinfunction "EN_1") (pintype "input"))
      (node (ref "U55") (pin "1") (pinfunction "EN_1") (pintype "input"))
      (node (ref "U56") (pin "1") (pinfunction "EN_1") (pintype "input"))
      (node (ref "U57") (pin "1") (pinfunction "EN_1") (pintype "input"))
      (node (ref "U58") (pin "1") (pinfunction "EN_1") (pintype "input"))
      (node (ref "U59") (pin "1") (pinfunction "EN_1") (pintype "input"))
      (node (ref "U6") (pin "1") (pinfunction "EN_1") (pintype "input"))
      (node (ref "U60") (pin "1") (pinfunction "EN_1") (pintype "input"))
      (node (ref "U61") (pin "1") (pinfunction "EN_1") (pintype "input"))
      (node (ref "U62") (pin "1") (pinfunction "EN_1") (pintype "input"))
      (node (ref "U63") (pin "1") (pinfunction "EN_1") (pintype "input"))
      (node (ref "U64") (pin "1") (pinfunction "EN_1") (pintype "input"))
      (node (ref "U7") (pin "1") (pinfunction "EN_1") (pintype "input"))
      (node (ref "U8") (pin "1") (pinfunction "EN_1") (pintype "input"))
      (node (ref "U9") (pin "1") (pinfunction "EN_1") (pintype "input"))
    )
    (net (code "6") (name "/FPGA-EN") (class "Default")
      (node (ref "JP2") (pin "1") (pinfunction "1_1") (pintype "passive"))
      (node (ref "JUMPER") (pin "3") (pinfunction "3_3") (pintype "passive"))
    )
    (net (code "7") (name "/ID") (class "Default")
      (node (ref "X1") (pin "4") (pinfunction "4_4") (pintype "passive"))
    )
    (net (code "8") (name "/IN0") (class "Default")
      (node (ref "JP1") (pin "3") (pinfunction "3_3") (pintype "passive"))
      (node (ref "U1") (pin "2") (pinfunction "IN_2") (pintype "input"))
    )
    (net (code "9") (name "/IN1") (class "Default")
      (node (ref "JP1") (pin "5") (pinfunction "5_5") (pintype "passive"))
      (node (ref "U2") (pin "2") (pinfunction "IN_2") (pintype "input"))
    )
    (net (code "10") (name "/IN2") (class "Default")
      (node (ref "JP1") (pin "7") (pinfunction "7_7") (pintype "passive"))
      (node (ref "U3") (pin "2") (pinfunction "IN_2") (pintype "input"))
    )
    (net (code "11") (name "/IN3") (class "Default")
      (node (ref "JP1") (pin "9") (pinfunction "9_9") (pintype "passive"))
      (node (ref "U4") (pin "2") (pinfunction "IN_2") (pintype "input"))
    )
    (net (code "12") (name "/IN4") (class "Default")
      (node (ref "JP1") (pin "13") (pinfunction "13_13") (pintype "passive"))
      (node (ref "U5") (pin "2") (pinfunction "IN_2") (pintype "input"))
    )
    (net (code "13") (name "/IN5") (class "Default")
      (node (ref "JP1") (pin "15") (pinfunction "15_15") (pintype "passive"))
      (node (ref "U6") (pin "2") (pinfunction "IN_2") (pintype "input"))
    )
    (net (code "14") (name "/IN6") (class "Default")
      (node (ref "JP1") (pin "17") (pinfunction "17_17") (pintype "passive"))
      (node (ref "U7") (pin "2") (pinfunction "IN_2") (pintype "input"))
    )
    (net (code "15") (name "/IN7") (class "Default")
      (node (ref "JP1") (pin "19") (pinfunction "19_19") (pintype "passive"))
      (node (ref "U8") (pin "2") (pinfunction "IN_2") (pintype "input"))
    )
    (net (code "16") (name "/IN8") (class "Default")
      (node (ref "JP1") (pin "21") (pinfunction "21_21") (pintype "passive"))
      (node (ref "U9") (pin "2") (pinfunction "IN_2") (pintype "input"))
    )
    (net (code "17") (name "/IN9") (class "Default")
      (node (ref "JP1") (pin "23") (pinfunction "23_23") (pintype "passive"))
      (node (ref "U10") (pin "2") (pinfunction "IN_2") (pintype "input"))
    )
    (net (code "18") (name "/IN10") (class "Default")
      (node (ref "JP1") (pin "25") (pinfunction "25_25") (pintype "passive"))
      (node (ref "U11") (pin "2") (pinfunction "IN_2") (pintype "input"))
    )
    (net (code "19") (name "/IN11") (class "Default")
      (node (ref "JP1") (pin "27") (pinfunction "27_27") (pintype "passive"))
      (node (ref "U12") (pin "2") (pinfunction "IN_2") (pintype "input"))
    )
    (net (code "20") (name "/IN12") (class "Default")
      (node (ref "JP1") (pin "31") (pinfunction "31_31") (pintype "passive"))
      (node (ref "U13") (pin "2") (pinfunction "IN_2") (pintype "input"))
    )
    (net (code "21") (name "/IN13") (class "Default")
      (node (ref "JP1") (pin "33") (pinfunction "33_33") (pintype "passive"))
      (node (ref "U14") (pin "2") (pinfunction "IN_2") (pintype "input"))
    )
    (net (code "22") (name "/IN14") (class "Default")
      (node (ref "JP1") (pin "35") (pinfunction "35_35") (pintype "passive"))
      (node (ref "U15") (pin "2") (pinfunction "IN_2") (pintype "input"))
    )
    (net (code "23") (name "/IN15") (class "Default")
      (node (ref "JP1") (pin "37") (pinfunction "37_37") (pintype "passive"))
      (node (ref "U16") (pin "2") (pinfunction "IN_2") (pintype "input"))
    )
    (net (code "24") (name "/IN16") (class "Default")
      (node (ref "JP1") (pin "40") (pinfunction "40_40") (pintype "passive"))
      (node (ref "U17") (pin "2") (pinfunction "IN_2") (pintype "input"))
    )
    (net (code "25") (name "/IN17") (class "Default")
      (node (ref "JP1") (pin "38") (pinfunction "38_38") (pintype "passive"))
      (node (ref "U18") (pin "2") (pinfunction "IN_2") (pintype "input"))
    )
    (net (code "26") (name "/IN18") (class "Default")
      (node (ref "JP1") (pin "36") (pinfunction "36_36") (pintype "passive"))
      (node (ref "U19") (pin "2") (pinfunction "IN_2") (pintype "input"))
    )
    (net (code "27") (name "/IN19") (class "Default")
      (node (ref "JP1") (pin "34") (pinfunction "34_34") (pintype "passive"))
      (node (ref "U20") (pin "2") (pinfunction "IN_2") (pintype "input"))
    )
    (net (code "28") (name "/IN20") (class "Default")
      (node (ref "JP1") (pin "32") (pinfunction "32_32") (pintype "passive"))
      (node (ref "U21") (pin "2") (pinfunction "IN_2") (pintype "input"))
    )
    (net (code "29") (name "/IN21") (class "Default")
      (node (ref "JP1") (pin "28") (pinfunction "28_28") (pintype "passive"))
      (node (ref "U22") (pin "2") (pinfunction "IN_2") (pintype "input"))
    )
    (net (code "30") (name "/IN22") (class "Default")
      (node (ref "JP1") (pin "26") (pinfunction "26_26") (pintype "passive"))
      (node (ref "U23") (pin "2") (pinfunction "IN_2") (pintype "input"))
    )
    (net (code "31") (name "/IN23") (class "Default")
      (node (ref "JP1") (pin "24") (pinfunction "24_24") (pintype "passive"))
      (node (ref "U24") (pin "2") (pinfunction "IN_2") (pintype "input"))
    )
    (net (code "32") (name "/IN24") (class "Default")
      (node (ref "JP1") (pin "22") (pinfunction "22_22") (pintype "passive"))
      (node (ref "U25") (pin "2") (pinfunction "IN_2") (pintype "input"))
    )
    (net (code "33") (name "/IN25") (class "Default")
      (node (ref "JP1") (pin "20") (pinfunction "20_20") (pintype "passive"))
      (node (ref "U26") (pin "2") (pinfunction "IN_2") (pintype "input"))
    )
    (net (code "34") (name "/IN26") (class "Default")
      (node (ref "JP1") (pin "18") (pinfunction "18_18") (pintype "passive"))
      (node (ref "U27") (pin "2") (pinfunction "IN_2") (pintype "input"))
    )
    (net (code "35") (name "/IN27") (class "Default")
      (node (ref "JP1") (pin "16") (pinfunction "16_16") (pintype "passive"))
      (node (ref "U28") (pin "2") (pinfunction "IN_2") (pintype "input"))
    )
    (net (code "36") (name "/IN28") (class "Default")
      (node (ref "JP1") (pin "14") (pinfunction "14_14") (pintype "passive"))
      (node (ref "U29") (pin "2") (pinfunction "IN_2") (pintype "input"))
    )
    (net (code "37") (name "/IN29") (class "Default")
      (node (ref "JP1") (pin "10") (pinfunction "10_10") (pintype "passive"))
      (node (ref "U30") (pin "2") (pinfunction "IN_2") (pintype "input"))
    )
    (net (code "38") (name "/IN30") (class "Default")
      (node (ref "JP1") (pin "8") (pinfunction "8_8") (pintype "passive"))
      (node (ref "U31") (pin "2") (pinfunction "IN_2") (pintype "input"))
    )
    (net (code "39") (name "/IN31") (class "Default")
      (node (ref "JP1") (pin "6") (pinfunction "6_6") (pintype "passive"))
      (node (ref "U32") (pin "2") (pinfunction "IN_2") (pintype "input"))
    )
    (net (code "40") (name "/IN32") (class "Default")
      (node (ref "JP2") (pin "3") (pinfunction "3_3") (pintype "passive"))
      (node (ref "U33") (pin "2") (pinfunction "IN_2") (pintype "input"))
    )
    (net (code "41") (name "/IN33") (class "Default")
      (node (ref "JP2") (pin "5") (pinfunction "5_5") (pintype "passive"))
      (node (ref "U34") (pin "2") (pinfunction "IN_2") (pintype "input"))
    )
    (net (code "42") (name "/IN34") (class "Default")
      (node (ref "JP2") (pin "7") (pinfunction "7_7") (pintype "passive"))
      (node (ref "U35") (pin "2") (pinfunction "IN_2") (pintype "input"))
    )
    (net (code "43") (name "/IN35") (class "Default")
      (node (ref "JP2") (pin "9") (pinfunction "9_9") (pintype "passive"))
      (node (ref "U36") (pin "2") (pinfunction "IN_2") (pintype "input"))
    )
    (net (code "44") (name "/IN36") (class "Default")
      (node (ref "JP2") (pin "13") (pinfunction "13_13") (pintype "passive"))
      (node (ref "U37") (pin "2") (pinfunction "IN_2") (pintype "input"))
    )
    (net (code "45") (name "/IN37") (class "Default")
      (node (ref "JP2") (pin "15") (pinfunction "15_15") (pintype "passive"))
      (node (ref "U38") (pin "2") (pinfunction "IN_2") (pintype "input"))
    )
    (net (code "46") (name "/IN38") (class "Default")
      (node (ref "JP2") (pin "17") (pinfunction "17_17") (pintype "passive"))
      (node (ref "U39") (pin "2") (pinfunction "IN_2") (pintype "input"))
    )
    (net (code "47") (name "/IN39") (class "Default")
      (node (ref "JP2") (pin "19") (pinfunction "19_19") (pintype "passive"))
      (node (ref "U40") (pin "2") (pinfunction "IN_2") (pintype "input"))
    )
    (net (code "48") (name "/IN40") (class "Default")
      (node (ref "JP2") (pin "21") (pinfunction "21_21") (pintype "passive"))
      (node (ref "U41") (pin "2") (pinfunction "IN_2") (pintype "input"))
    )
    (net (code "49") (name "/IN41") (class "Default")
      (node (ref "JP2") (pin "23") (pinfunction "23_23") (pintype "passive"))
      (node (ref "U42") (pin "2") (pinfunction "IN_2") (pintype "input"))
    )
    (net (code "50") (name "/IN42") (class "Default")
      (node (ref "JP2") (pin "25") (pinfunction "25_25") (pintype "passive"))
      (node (ref "U43") (pin "2") (pinfunction "IN_2") (pintype "input"))
    )
    (net (code "51") (name "/IN43") (class "Default")
      (node (ref "JP2") (pin "27") (pinfunction "27_27") (pintype "passive"))
      (node (ref "U44") (pin "2") (pinfunction "IN_2") (pintype "input"))
    )
    (net (code "52") (name "/IN44") (class "Default")
      (node (ref "JP2") (pin "31") (pinfunction "31_31") (pintype "passive"))
      (node (ref "U45") (pin "2") (pinfunction "IN_2") (pintype "input"))
    )
    (net (code "53") (name "/IN45") (class "Default")
      (node (ref "JP2") (pin "33") (pinfunction "33_33") (pintype "passive"))
      (node (ref "U46") (pin "2") (pinfunction "IN_2") (pintype "input"))
    )
    (net (code "54") (name "/IN46") (class "Default")
      (node (ref "JP2") (pin "35") (pinfunction "35_35") (pintype "passive"))
      (node (ref "U47") (pin "2") (pinfunction "IN_2") (pintype "input"))
    )
    (net (code "55") (name "/IN47") (class "Default")
      (node (ref "JP2") (pin "37") (pinfunction "37_37") (pintype "passive"))
      (node (ref "U48") (pin "2") (pinfunction "IN_2") (pintype "input"))
    )
    (net (code "56") (name "/IN48") (class "Default")
      (node (ref "JP2") (pin "40") (pinfunction "40_40") (pintype "passive"))
      (node (ref "U49") (pin "2") (pinfunction "IN_2") (pintype "input"))
    )
    (net (code "57") (name "/IN49") (class "Default")
      (node (ref "JP2") (pin "38") (pinfunction "38_38") (pintype "passive"))
      (node (ref "U50") (pin "2") (pinfunction "IN_2") (pintype "input"))
    )
    (net (code "58") (name "/IN50") (class "Default")
      (node (ref "JP2") (pin "36") (pinfunction "36_36") (pintype "passive"))
      (node (ref "U51") (pin "2") (pinfunction "IN_2") (pintype "input"))
    )
    (net (code "59") (name "/IN51") (class "Default")
      (node (ref "JP2") (pin "34") (pinfunction "34_34") (pintype "passive"))
      (node (ref "U52") (pin "2") (pinfunction "IN_2") (pintype "input"))
    )
    (net (code "60") (name "/IN52") (class "Default")
      (node (ref "JP2") (pin "32") (pinfunction "32_32") (pintype "passive"))
      (node (ref "U53") (pin "2") (pinfunction "IN_2") (pintype "input"))
    )
    (net (code "61") (name "/IN53") (class "Default")
      (node (ref "JP2") (pin "28") (pinfunction "28_28") (pintype "passive"))
      (node (ref "U54") (pin "2") (pinfunction "IN_2") (pintype "input"))
    )
    (net (code "62") (name "/IN54") (class "Default")
      (node (ref "JP2") (pin "26") (pinfunction "26_26") (pintype "passive"))
      (node (ref "U55") (pin "2") (pinfunction "IN_2") (pintype "input"))
    )
    (net (code "63") (name "/IN55") (class "Default")
      (node (ref "JP2") (pin "24") (pinfunction "24_24") (pintype "passive"))
      (node (ref "U56") (pin "2") (pinfunction "IN_2") (pintype "input"))
    )
    (net (code "64") (name "/IN56") (class "Default")
      (node (ref "JP2") (pin "22") (pinfunction "22_22") (pintype "passive"))
      (node (ref "U57") (pin "2") (pinfunction "IN_2") (pintype "input"))
    )
    (net (code "65") (name "/IN57") (class "Default")
      (node (ref "JP2") (pin "20") (pinfunction "20_20") (pintype "passive"))
      (node (ref "U58") (pin "2") (pinfunction "IN_2") (pintype "input"))
    )
    (net (code "66") (name "/IN58") (class "Default")
      (node (ref "JP2") (pin "18") (pinfunction "18_18") (pintype "passive"))
      (node (ref "U59") (pin "2") (pinfunction "IN_2") (pintype "input"))
    )
    (net (code "67") (name "/IN59") (class "Default")
      (node (ref "JP2") (pin "16") (pinfunction "16_16") (pintype "passive"))
      (node (ref "U60") (pin "2") (pinfunction "IN_2") (pintype "input"))
    )
    (net (code "68") (name "/IN60") (class "Default")
      (node (ref "JP2") (pin "14") (pinfunction "14_14") (pintype "passive"))
      (node (ref "U61") (pin "2") (pinfunction "IN_2") (pintype "input"))
    )
    (net (code "69") (name "/IN61") (class "Default")
      (node (ref "JP2") (pin "10") (pinfunction "10_10") (pintype "passive"))
      (node (ref "U62") (pin "2") (pinfunction "IN_2") (pintype "input"))
    )
    (net (code "70") (name "/IN62") (class "Default")
      (node (ref "JP2") (pin "8") (pinfunction "8_8") (pintype "passive"))
      (node (ref "U63") (pin "2") (pinfunction "IN_2") (pintype "input"))
    )
    (net (code "71") (name "/IN63") (class "Default")
      (node (ref "JP2") (pin "6") (pinfunction "6_6") (pintype "passive"))
      (node (ref "U64") (pin "2") (pinfunction "IN_2") (pintype "input"))
    )
    (net (code "81") (name "/OSCI") (class "Default")
      (node (ref "C140") (pin "1") (pinfunction "1_1") (pintype "passive"))
      (node (ref "Q1") (pin "1") (pinfunction "1_1") (pintype "passive"))
      (node (ref "U66") (pin "27") (pinfunction "OSCI_27") (pintype "bidirectional"))
    )
    (net (code "82") (name "/OSCO") (class "Default")
      (node (ref "C139") (pin "1") (pinfunction "1_1") (pintype "passive"))
      (node (ref "Q1") (pin "2") (pinfunction "2_2") (pintype "passive"))
      (node (ref "U66") (pin "28") (pinfunction "OSCO_28") (pintype "bidirectional"))
    )
    (net (code "83") (name "/OUT0") (class "Default")
      (node (ref "C68") (pin "2") (pinfunction "2_2") (pintype "passive"))
      (node (ref "SV1") (pin "1") (pinfunction "1_1") (pintype "passive"))
    )
    (net (code "84") (name "/OUT1") (class "Default")
      (node (ref "C69") (pin "2") (pinfunction "2_2") (pintype "passive"))
      (node (ref "SV1") (pin "3") (pinfunction "3_3") (pintype "passive"))
    )
    (net (code "85") (name "/OUT2") (class "Default")
      (node (ref "C70") (pin "2") (pinfunction "2_2") (pintype "passive"))
      (node (ref "SV1") (pin "5") (pinfunction "5_5") (pintype "passive"))
    )
    (net (code "86") (name "/OUT3") (class "Default")
      (node (ref "C71") (pin "2") (pinfunction "2_2") (pintype "passive"))
      (node (ref "SV1") (pin "7") (pinfunction "7_7") (pintype "passive"))
    )
    (net (code "87") (name "/OUT4") (class "Default")
      (node (ref "C72") (pin "2") (pinfunction "2_2") (pintype "passive"))
      (node (ref "SV1") (pin "9") (pinfunction "9_9") (pintype "passive"))
    )
    (net (code "88") (name "/OUT5") (class "Default")
      (node (ref "C73") (pin "2") (pinfunction "2_2") (pintype "passive"))
      (node (ref "SV1") (pin "11") (pinfunction "11_11") (pintype "passive"))
    )
    (net (code "89") (name "/OUT6") (class "Default")
      (node (ref "C74") (pin "2") (pinfunction "2_2") (pintype "passive"))
      (node (ref "SV1") (pin "13") (pinfunction "13_13") (pintype "passive"))
    )
    (net (code "90") (name "/OUT7") (class "Default")
      (node (ref "C75") (pin "2") (pinfunction "2_2") (pintype "passive"))
      (node (ref "SV1") (pin "15") (pinfunction "15_15") (pintype "passive"))
    )
    (net (code "91") (name "/OUT8") (class "Default")
      (node (ref "C76") (pin "2") (pinfunction "2_2") (pintype "passive"))
      (node (ref "SV1") (pin "17") (pinfunction "17_17") (pintype "passive"))
    )
    (net (code "92") (name "/OUT9") (class "Default")
      (node (ref "C77") (pin "2") (pinfunction "2_2") (pintype "passive"))
      (node (ref "SV1") (pin "19") (pinfunction "19_19") (pintype "passive"))
    )
    (net (code "93") (name "/OUT10") (class "Default")
      (node (ref "C78") (pin "2") (pinfunction "2_2") (pintype "passive"))
      (node (ref "SV1") (pin "21") (pinfunction "21_21") (pintype "passive"))
    )
    (net (code "94") (name "/OUT11") (class "Default")
      (node (ref "C79") (pin "2") (pinfunction "2_2") (pintype "passive"))
      (node (ref "SV1") (pin "23") (pinfunction "23_23") (pintype "passive"))
    )
    (net (code "95") (name "/OUT12") (class "Default")
      (node (ref "C80") (pin "2") (pinfunction "2_2") (pintype "passive"))
      (node (ref "SV1") (pin "25") (pinfunction "25_25") (pintype "passive"))
    )
    (net (code "96") (name "/OUT13") (class "Default")
      (node (ref "C81") (pin "2") (pinfunction "2_2") (pintype "passive"))
      (node (ref "SV1") (pin "27") (pinfunction "27_27") (pintype "passive"))
    )
    (net (code "97") (name "/OUT14") (class "Default")
      (node (ref "C82") (pin "2") (pinfunction "2_2") (pintype "passive"))
      (node (ref "SV1") (pin "29") (pinfunction "29_29") (pintype "passive"))
    )
    (net (code "98") (name "/OUT15") (class "Default")
      (node (ref "C83") (pin "2") (pinfunction "2_2") (pintype "passive"))
      (node (ref "SV1") (pin "31") (pinfunction "31_31") (pintype "passive"))
    )
    (net (code "99") (name "/OUT16") (class "Default")
      (node (ref "C84") (pin "2") (pinfunction "2_2") (pintype "passive"))
      (node (ref "SV2") (pin "1") (pinfunction "1_1") (pintype "passive"))
    )
    (net (code "100") (name "/OUT17") (class "Default")
      (node (ref "C85") (pin "2") (pinfunction "2_2") (pintype "passive"))
      (node (ref "SV2") (pin "3") (pinfunction "3_3") (pintype "passive"))
    )
    (net (code "101") (name "/OUT18") (class "Default")
      (node (ref "C86") (pin "2") (pinfunction "2_2") (pintype "passive"))
      (node (ref "SV2") (pin "5") (pinfunction "5_5") (pintype "passive"))
    )
    (net (code "102") (name "/OUT19") (class "Default")
      (node (ref "C87") (pin "2") (pinfunction "2_2") (pintype "passive"))
      (node (ref "SV2") (pin "7") (pinfunction "7_7") (pintype "passive"))
    )
    (net (code "103") (name "/OUT20") (class "Default")
      (node (ref "C88") (pin "2") (pinfunction "2_2") (pintype "passive"))
      (node (ref "SV2") (pin "9") (pinfunction "9_9") (pintype "passive"))
    )
    (net (code "104") (name "/OUT21") (class "Default")
      (node (ref "C89") (pin "2") (pinfunction "2_2") (pintype "passive"))
      (node (ref "SV2") (pin "11") (pinfunction "11_11") (pintype "passive"))
    )
    (net (code "105") (name "/OUT22") (class "Default")
      (node (ref "C90") (pin "2") (pinfunction "2_2") (pintype "passive"))
      (node (ref "SV2") (pin "13") (pinfunction "13_13") (pintype "passive"))
    )
    (net (code "106") (name "/OUT23") (class "Default")
      (node (ref "C91") (pin "2") (pinfunction "2_2") (pintype "passive"))
      (node (ref "SV2") (pin "15") (pinfunction "15_15") (pintype "passive"))
    )
    (net (code "107") (name "/OUT24") (class "Default")
      (node (ref "C92") (pin "2") (pinfunction "2_2") (pintype "passive"))
      (node (ref "SV2") (pin "17") (pinfunction "17_17") (pintype "passive"))
    )
    (net (code "108") (name "/OUT25") (class "Default")
      (node (ref "C93") (pin "2") (pinfunction "2_2") (pintype "passive"))
      (node (ref "SV2") (pin "19") (pinfunction "19_19") (pintype "passive"))
    )
    (net (code "109") (name "/OUT26") (class "Default")
      (node (ref "C94") (pin "2") (pinfunction "2_2") (pintype "passive"))
      (node (ref "SV2") (pin "21") (pinfunction "21_21") (pintype "passive"))
    )
    (net (code "110") (name "/OUT27") (class "Default")
      (node (ref "C95") (pin "2") (pinfunction "2_2") (pintype "passive"))
      (node (ref "SV2") (pin "23") (pinfunction "23_23") (pintype "passive"))
    )
    (net (code "111") (name "/OUT28") (class "Default")
      (node (ref "C96") (pin "2") (pinfunction "2_2") (pintype "passive"))
      (node (ref "SV2") (pin "25") (pinfunction "25_25") (pintype "passive"))
    )
    (net (code "112") (name "/OUT29") (class "Default")
      (node (ref "C97") (pin "2") (pinfunction "2_2") (pintype "passive"))
      (node (ref "SV2") (pin "27") (pinfunction "27_27") (pintype "passive"))
    )
    (net (code "113") (name "/OUT30") (class "Default")
      (node (ref "C98") (pin "2") (pinfunction "2_2") (pintype "passive"))
      (node (ref "SV2") (pin "29") (pinfunction "29_29") (pintype "passive"))
    )
    (net (code "114") (name "/OUT31") (class "Default")
      (node (ref "C99") (pin "2") (pinfunction "2_2") (pintype "passive"))
      (node (ref "SV2") (pin "31") (pinfunction "31_31") (pintype "passive"))
    )
    (net (code "115") (name "/OUT32") (class "Default")
      (node (ref "C100") (pin "2") (pinfunction "2_2") (pintype "passive"))
      (node (ref "SV3") (pin "1") (pinfunction "1_1") (pintype "passive"))
    )
    (net (code "116") (name "/OUT33") (class "Default")
      (node (ref "C101") (pin "2") (pinfunction "2_2") (pintype "passive"))
      (node (ref "SV3") (pin "3") (pinfunction "3_3") (pintype "passive"))
    )
    (net (code "117") (name "/OUT34") (class "Default")
      (node (ref "C102") (pin "2") (pinfunction "2_2") (pintype "passive"))
      (node (ref "SV3") (pin "5") (pinfunction "5_5") (pintype "passive"))
    )
    (net (code "118") (name "/OUT35") (class "Default")
      (node (ref "C103") (pin "2") (pinfunction "2_2") (pintype "passive"))
      (node (ref "SV3") (pin "7") (pinfunction "7_7") (pintype "passive"))
    )
    (net (code "119") (name "/OUT36") (class "Default")
      (node (ref "C104") (pin "2") (pinfunction "2_2") (pintype "passive"))
      (node (ref "SV3") (pin "9") (pinfunction "9_9") (pintype "passive"))
    )
    (net (code "120") (name "/OUT37") (class "Default")
      (node (ref "C105") (pin "2") (pinfunction "2_2") (pintype "passive"))
      (node (ref "SV3") (pin "11") (pinfunction "11_11") (pintype "passive"))
    )
    (net (code "121") (name "/OUT38") (class "Default")
      (node (ref "C106") (pin "2") (pinfunction "2_2") (pintype "passive"))
      (node (ref "SV3") (pin "13") (pinfunction "13_13") (pintype "passive"))
    )
    (net (code "122") (name "/OUT39") (class "Default")
      (node (ref "C107") (pin "2") (pinfunction "2_2") (pintype "passive"))
      (node (ref "SV3") (pin "15") (pinfunction "15_15") (pintype "passive"))
    )
    (net (code "123") (name "/OUT40") (class "Default")
      (node (ref "C108") (pin "2") (pinfunction "2_2") (pintype "passive"))
      (node (ref "SV3") (pin "17") (pinfunction "17_17") (pintype "passive"))
    )
    (net (code "124") (name "/OUT41") (class "Default")
      (node (ref "C109") (pin "2") (pinfunction "2_2") (pintype "passive"))
      (node (ref "SV3") (pin "19") (pinfunction "19_19") (pintype "passive"))
    )
    (net (code "125") (name "/OUT42") (class "Default")
      (node (ref "C110") (pin "2") (pinfunction "2_2") (pintype "passive"))
      (node (ref "SV3") (pin "21") (pinfunction "21_21") (pintype "passive"))
    )
    (net (code "126") (name "/OUT43") (class "Default")
      (node (ref "C111") (pin "2") (pinfunction "2_2") (pintype "passive"))
      (node (ref "SV3") (pin "23") (pinfunction "23_23") (pintype "passive"))
    )
    (net (code "127") (name "/OUT44") (class "Default")
      (node (ref "C112") (pin "2") (pinfunction "2_2") (pintype "passive"))
      (node (ref "SV3") (pin "25") (pinfunction "25_25") (pintype "passive"))
    )
    (net (code "128") (name "/OUT45") (class "Default")
      (node (ref "C113") (pin "2") (pinfunction "2_2") (pintype "passive"))
      (node (ref "SV3") (pin "27") (pinfunction "27_27") (pintype "passive"))
    )
    (net (code "129") (name "/OUT46") (class "Default")
      (node (ref "C114") (pin "2") (pinfunction "2_2") (pintype "passive"))
      (node (ref "SV3") (pin "29") (pinfunction "29_29") (pintype "passive"))
    )
    (net (code "130") (name "/OUT47") (class "Default")
      (node (ref "C115") (pin "2") (pinfunction "2_2") (pintype "passive"))
      (node (ref "SV3") (pin "31") (pinfunction "31_31") (pintype "passive"))
    )
    (net (code "131") (name "/OUT48") (class "Default")
      (node (ref "C116") (pin "2") (pinfunction "2_2") (pintype "passive"))
      (node (ref "SV4") (pin "1") (pinfunction "1_1") (pintype "passive"))
    )
    (net (code "132") (name "/OUT49") (class "Default")
      (node (ref "C117") (pin "2") (pinfunction "2_2") (pintype "passive"))
      (node (ref "SV4") (pin "3") (pinfunction "3_3") (pintype "passive"))
    )
    (net (code "133") (name "/OUT50") (class "Default")
      (node (ref "C118") (pin "2") (pinfunction "2_2") (pintype "passive"))
      (node (ref "SV4") (pin "5") (pinfunction "5_5") (pintype "passive"))
    )
    (net (code "134") (name "/OUT51") (class "Default")
      (node (ref "C119") (pin "2") (pinfunction "2_2") (pintype "passive"))
      (node (ref "SV4") (pin "7") (pinfunction "7_7") (pintype "passive"))
    )
    (net (code "135") (name "/OUT52") (class "Default")
      (node (ref "C120") (pin "2") (pinfunction "2_2") (pintype "passive"))
      (node (ref "SV4") (pin "9") (pinfunction "9_9") (pintype "passive"))
    )
    (net (code "136") (name "/OUT53") (class "Default")
      (node (ref "C121") (pin "2") (pinfunction "2_2") (pintype "passive"))
      (node (ref "SV4") (pin "11") (pinfunction "11_11") (pintype "passive"))
    )
    (net (code "137") (name "/OUT54") (class "Default")
      (node (ref "C122") (pin "2") (pinfunction "2_2") (pintype "passive"))
      (node (ref "SV4") (pin "13") (pinfunction "13_13") (pintype "passive"))
    )
    (net (code "138") (name "/OUT55") (class "Default")
      (node (ref "C123") (pin "2") (pinfunction "2_2") (pintype "passive"))
      (node (ref "SV4") (pin "15") (pinfunction "15_15") (pintype "passive"))
    )
    (net (code "139") (name "/OUT56") (class "Default")
      (node (ref "C124") (pin "2") (pinfunction "2_2") (pintype "passive"))
      (node (ref "SV4") (pin "17") (pinfunction "17_17") (pintype "passive"))
    )
    (net (code "140") (name "/OUT57") (class "Default")
      (node (ref "C125") (pin "2") (pinfunction "2_2") (pintype "passive"))
      (node (ref "SV4") (pin "19") (pinfunction "19_19") (pintype "passive"))
    )
    (net (code "141") (name "/OUT58") (class "Default")
      (node (ref "C126") (pin "2") (pinfunction "2_2") (pintype "passive"))
      (node (ref "SV4") (pin "21") (pinfunction "21_21") (pintype "passive"))
    )
    (net (code "142") (name "/OUT59") (class "Default")
      (node (ref "C127") (pin "2") (pinfunction "2_2") (pintype "passive"))
      (node (ref "SV4") (pin "23") (pinfunction "23_23") (pintype "passive"))
    )
    (net (code "143") (name "/OUT60") (class "Default")
      (node (ref "C128") (pin "2") (pinfunction "2_2") (pintype "passive"))
      (node (ref "SV4") (pin "25") (pinfunction "25_25") (pintype "passive"))
    )
    (net (code "144") (name "/OUT61") (class "Default")
      (node (ref "C129") (pin "2") (pinfunction "2_2") (pintype "passive"))
      (node (ref "SV4") (pin "27") (pinfunction "27_27") (pintype "passive"))
    )
    (net (code "145") (name "/OUT62") (class "Default")
      (node (ref "C1130") (pin "2") (pinfunction "2_2") (pintype "passive"))
      (node (ref "SV4") (pin "29") (pinfunction "29_29") (pintype "passive"))
    )
    (net (code "146") (name "/OUT63") (class "Default")
      (node (ref "C1131") (pin "2") (pinfunction "2_2") (pintype "passive"))
      (node (ref "SV4") (pin "31") (pinfunction "31_31") (pintype "passive"))
    )
    (net (code "159") (name "/RX") (class "Default")
      (node (ref "JP1") (pin "1") (pinfunction "1_1") (pintype "passive"))
      (node (ref "U66") (pin "5") (pinfunction "RXD_5") (pintype "bidirectional"))
    )
    (net (code "160") (name "/TX") (class "Default")
      (node (ref "JP1") (pin "2") (pinfunction "2_2") (pintype "passive"))
      (node (ref "U66") (pin "1") (pinfunction "TXD_1") (pintype "bidirectional"))
    )
    (net (code "161") (name "/TXDEN") (class "Default")
      (node (ref "U66") (pin "13") (pinfunction "CBUS2_13") (pintype "bidirectional"))
    )
    (net (code "162") (name "/VBUS") (class "Default")
      (node (ref "C138") (pin "1") (pinfunction "1_1") (pintype "passive"))
      (node (ref "L1") (pin "A") (pinfunction "1_A") (pintype "passive"))
      (node (ref "R8") (pin "1") (pinfunction "1_1") (pintype "passive"))
      (node (ref "X1") (pin "1") (pinfunction "1_1") (pintype "passive"))
    )
    (net (code "163") (name "/VCC") (class "Default")
      (node (ref "C137") (pin "1") (pinfunction "1_1") (pintype "passive"))
      (node (ref "C141") (pin "+") (pinfunction "+_+") (pintype "passive"))
      (node (ref "L2") (pin "C") (pinfunction "2_C") (pintype "passive"))
      (node (ref "U66") (pin "20") (pinfunction "VCC_20") (pintype "power_in"))
    )
    (net (code "164") (name "/VDD") (class "Default")
      (node (ref "C10") (pin "1") (pinfunction "1_1") (pintype "passive"))
      (node (ref "C11") (pin "1") (pinfunction "1_1") (pintype "passive"))
      (node (ref "C12") (pin "1") (pinfunction "1_1") (pintype "passive"))
      (node (ref "C13") (pin "1") (pinfunction "1_1") (pintype "passive"))
      (node (ref "C133") (pin "+") (pinfunction "+_+") (pintype "passive"))
      (node (ref "C134") (pin "+") (pinfunction "+_+") (pintype "passive"))
      (node (ref "C135") (pin "+") (pinfunction "+_+") (pintype "passive"))
      (node (ref "C14") (pin "1") (pinfunction "1_1") (pintype "passive"))
      (node (ref "C15") (pin "1") (pinfunction "1_1") (pintype "passive"))
      (node (ref "C16") (pin "1") (pinfunction "1_1") (pintype "passive"))
      (node (ref "C17") (pin "1") (pinfunction "1_1") (pintype "passive"))
      (node (ref "C18") (pin "1") (pinfunction "1_1") (pintype "passive"))
      (node (ref "C19") (pin "1") (pinfunction "1_1") (pintype "passive"))
      (node (ref "C2") (pin "1") (pinfunction "1_1") (pintype "passive"))
      (node (ref "C20") (pin "1") (pinfunction "1_1") (pintype "passive"))
      (node (ref "C21") (pin "1") (pinfunction "1_1") (pintype "passive"))
      (node (ref "C22") (pin "1") (pinfunction "1_1") (pintype "passive"))
      (node (ref "C23") (pin "1") (pinfunction "1_1") (pintype "passive"))
      (node (ref "C24") (pin "1") (pinfunction "1_1") (pintype "passive"))
      (node (ref "C25") (pin "1") (pinfunction "1_1") (pintype "passive"))
      (node (ref "C26") (pin "1") (pinfunction "1_1") (pintype "passive"))
      (node (ref "C27") (pin "1") (pinfunction "1_1") (pintype "passive"))
      (node (ref "C28") (pin "1") (pinfunction "1_1") (pintype "passive"))
      (node (ref "C29") (pin "1") (pinfunction "1_1") (pintype "passive"))
      (node (ref "C3") (pin "1") (pinfunction "1_1") (pintype "passive"))
      (node (ref "C30") (pin "1") (pinfunction "1_1") (pintype "passive"))
      (node (ref "C31") (pin "1") (pinfunction "1_1") (pintype "passive"))
      (node (ref "C32") (pin "1") (pinfunction "1_1") (pintype "passive"))
      (node (ref "C33") (pin "1") (pinfunction "1_1") (pintype "passive"))
      (node (ref "C34") (pin "1") (pinfunction "1_1") (pintype "passive"))
      (node (ref "C35") (pin "1") (pinfunction "1_1") (pintype "passive"))
      (node (ref "C36") (pin "1") (pinfunction "1_1") (pintype "passive"))
      (node (ref "C37") (pin "1") (pinfunction "1_1") (pintype "passive"))
      (node (ref "C38") (pin "1") (pinfunction "1_1") (pintype "passive"))
      (node (ref "C39") (pin "1") (pinfunction "1_1") (pintype "passive"))
      (node (ref "C4") (pin "1") (pinfunction "1_1") (pintype "passive"))
      (node (ref "C40") (pin "1") (pinfunction "1_1") (pintype "passive"))
      (node (ref "C41") (pin "1") (pinfunction "1_1") (pintype "passive"))
      (node (ref "C42") (pin "1") (pinfunction "1_1") (pintype "passive"))
      (node (ref "C43") (pin "1") (pinfunction "1_1") (pintype "passive"))
      (node (ref "C44") (pin "1") (pinfunction "1_1") (pintype "passive"))
      (node (ref "C45") (pin "1") (pinfunction "1_1") (pintype "passive"))
      (node (ref "C46") (pin "1") (pinfunction "1_1") (pintype "passive"))
      (node (ref "C47") (pin "1") (pinfunction "1_1") (pintype "passive"))
      (node (ref "C48") (pin "1") (pinfunction "1_1") (pintype "passive"))
      (node (ref "C49") (pin "1") (pinfunction "1_1") (pintype "passive"))
      (node (ref "C5") (pin "1") (pinfunction "1_1") (pintype "passive"))
      (node (ref "C50") (pin "1") (pinfunction "1_1") (pintype "passive"))
      (node (ref "C51") (pin "1") (pinfunction "1_1") (pintype "passive"))
      (node (ref "C52") (pin "1") (pinfunction "1_1") (pintype "passive"))
      (node (ref "C53") (pin "1") (pinfunction "1_1") (pintype "passive"))
      (node (ref "C54") (pin "1") (pinfunction "1_1") (pintype "passive"))
      (node (ref "C55") (pin "1") (pinfunction "1_1") (pintype "passive"))
      (node (ref "C56") (pin "1") (pinfunction "1_1") (pintype "passive"))
      (node (ref "C57") (pin "1") (pinfunction "1_1") (pintype "passive"))
      (node (ref "C58") (pin "1") (pinfunction "1_1") (pintype "passive"))
      (node (ref "C59") (pin "1") (pinfunction "1_1") (pintype "passive"))
      (node (ref "C6") (pin "1") (pinfunction "1_1") (pintype "passive"))
      (node (ref "C60") (pin "1") (pinfunction "1_1") (pintype "passive"))
      (node (ref "C61") (pin "1") (pinfunction "1_1") (pintype "passive"))
      (node (ref "C62") (pin "1") (pinfunction "1_1") (pintype "passive"))
      (node (ref "C63") (pin "1") (pinfunction "1_1") (pintype "passive"))
      (node (ref "C64") (pin "1") (pinfunction "1_1") (pintype "passive"))
      (node (ref "C65") (pin "1") (pinfunction "1_1") (pintype "passive"))
      (node (ref "C66") (pin "1") (pinfunction "1_1") (pintype "passive"))
      (node (ref "C67") (pin "1") (pinfunction "1_1") (pintype "passive"))
      (node (ref "C7") (pin "1") (pinfunction "1_1") (pintype "passive"))
      (node (ref "C8") (pin "1") (pinfunction "1_1") (pintype "passive"))
      (node (ref "C9") (pin "1") (pinfunction "1_1") (pintype "passive"))
      (node (ref "T1") (pin "5") (pinfunction "D_5") (pintype "passive"))
      (node (ref "T1") (pin "6") (pinfunction "D_6") (pintype "passive"))
      (node (ref "U1") (pin "3") (pinfunction "VDD_3") (pintype "power_in"))
      (node (ref "U10") (pin "3") (pinfunction "VDD_3") (pintype "power_in"))
      (node (ref "U11") (pin "3") (pinfunction "VDD_3") (pintype "power_in"))
      (node (ref "U12") (pin "3") (pinfunction "VDD_3") (pintype "power_in"))
      (node (ref "U13") (pin "3") (pinfunction "VDD_3") (pintype "power_in"))
      (node (ref "U14") (pin "3") (pinfunction "VDD_3") (pintype "power_in"))
      (node (ref "U15") (pin "3") (pinfunction "VDD_3") (pintype "power_in"))
      (node (ref "U16") (pin "3") (pinfunction "VDD_3") (pintype "power_in"))
      (node (ref "U17") (pin "3") (pinfunction "VDD_3") (pintype "power_in"))
      (node (ref "U18") (pin "3") (pinfunction "VDD_3") (pintype "power_in"))
      (node (ref "U19") (pin "3") (pinfunction "VDD_3") (pintype "power_in"))
      (node (ref "U2") (pin "3") (pinfunction "VDD_3") (pintype "power_in"))
      (node (ref "U20") (pin "3") (pinfunction "VDD_3") (pintype "power_in"))
      (node (ref "U21") (pin "3") (pinfunction "VDD_3") (pintype "power_in"))
      (node (ref "U22") (pin "3") (pinfunction "VDD_3") (pintype "power_in"))
      (node (ref "U23") (pin "3") (pinfunction "VDD_3") (pintype "power_in"))
      (node (ref "U24") (pin "3") (pinfunction "VDD_3") (pintype "power_in"))
      (node (ref "U25") (pin "3") (pinfunction "VDD_3") (pintype "power_in"))
      (node (ref "U26") (pin "3") (pinfunction "VDD_3") (pintype "power_in"))
      (node (ref "U27") (pin "3") (pinfunction "VDD_3") (pintype "power_in"))
      (node (ref "U28") (pin "3") (pinfunction "VDD_3") (pintype "power_in"))
      (node (ref "U29") (pin "3") (pinfunction "VDD_3") (pintype "power_in"))
      (node (ref "U3") (pin "3") (pinfunction "VDD_3") (pintype "power_in"))
      (node (ref "U30") (pin "3") (pinfunction "VDD_3") (pintype "power_in"))
      (node (ref "U31") (pin "3") (pinfunction "VDD_3") (pintype "power_in"))
      (node (ref "U32") (pin "3") (pinfunction "VDD_3") (pintype "power_in"))
      (node (ref "U33") (pin "3") (pinfunction "VDD_3") (pintype "power_in"))
      (node (ref "U34") (pin "3") (pinfunction "VDD_3") (pintype "power_in"))
      (node (ref "U35") (pin "3") (pinfunction "VDD_3") (pintype "power_in"))
      (node (ref "U36") (pin "3") (pinfunction "VDD_3") (pintype "power_in"))
      (node (ref "U37") (pin "3") (pinfunction "VDD_3") (pintype "power_in"))
      (node (ref "U38") (pin "3") (pinfunction "VDD_3") (pintype "power_in"))
      (node (ref "U39") (pin "3") (pinfunction "VDD_3") (pintype "power_in"))
      (node (ref "U4") (pin "3") (pinfunction "VDD_3") (pintype "power_in"))
      (node (ref "U40") (pin "3") (pinfunction "VDD_3") (pintype "power_in"))
      (node (ref "U41") (pin "3") (pinfunction "VDD_3") (pintype "power_in"))
      (node (ref "U42") (pin "3") (pinfunction "VDD_3") (pintype "power_in"))
      (node (ref "U43") (pin "3") (pinfunction "VDD_3") (pintype "power_in"))
      (node (ref "U44") (pin "3") (pinfunction "VDD_3") (pintype "power_in"))
      (node (ref "U45") (pin "3") (pinfunction "VDD_3") (pintype "power_in"))
      (node (ref "U46") (pin "3") (pinfunction "VDD_3") (pintype "power_in"))
      (node (ref "U47") (pin "3") (pinfunction "VDD_3") (pintype "power_in"))
      (node (ref "U48") (pin "3") (pinfunction "VDD_3") (pintype "power_in"))
      (node (ref "U49") (pin "3") (pinfunction "VDD_3") (pintype "power_in"))
      (node (ref "U5") (pin "3") (pinfunction "VDD_3") (pintype "power_in"))
      (node (ref "U50") (pin "3") (pinfunction "VDD_3") (pintype "power_in"))
      (node (ref "U51") (pin "3") (pinfunction "VDD_3") (pintype "power_in"))
      (node (ref "U52") (pin "3") (pinfunction "VDD_3") (pintype "power_in"))
      (node (ref "U53") (pin "3") (pinfunction "VDD_3") (pintype "power_in"))
      (node (ref "U54") (pin "3") (pinfunction "VDD_3") (pintype "power_in"))
      (node (ref "U55") (pin "3") (pinfunction "VDD_3") (pintype "power_in"))
      (node (ref "U56") (pin "3") (pinfunction "VDD_3") (pintype "power_in"))
      (node (ref "U57") (pin "3") (pinfunction "VDD_3") (pintype "power_in"))
      (node (ref "U58") (pin "3") (pinfunction "VDD_3") (pintype "power_in"))
      (node (ref "U59") (pin "3") (pinfunction "VDD_3") (pintype "power_in"))
      (node (ref "U6") (pin "3") (pinfunction "VDD_3") (pintype "power_in"))
      (node (ref "U60") (pin "3") (pinfunction "VDD_3") (pintype "power_in"))
      (node (ref "U61") (pin "3") (pinfunction "VDD_3") (pintype "power_in"))
      (node (ref "U62") (pin "3") (pinfunction "VDD_3") (pintype "power_in"))
      (node (ref "U63") (pin "3") (pinfunction "VDD_3") (pintype "power_in"))
      (node (ref "U64") (pin "3") (pinfunction "VDD_3") (pintype "power_in"))
      (node (ref "U65") (pin "7") (pinfunction "VOUT_7") (pintype "power_in"))
      (node (ref "U7") (pin "3") (pinfunction "VDD_3") (pintype "power_in"))
      (node (ref "U8") (pin "3") (pinfunction "VDD_3") (pintype "power_in"))
      (node (ref "U9") (pin "3") (pinfunction "VDD_3") (pintype "power_in"))
    )
    (net (code "165") (name "/VIN") (class "Default")
      (node (ref "J1") (pin "1") (pinfunction "1_1") (pintype "passive"))
      (node (ref "R1") (pin "2") (pinfunction "2_2") (pintype "passive"))
      (node (ref "R2") (pin "2") (pinfunction "2_2") (pintype "passive"))
      (node (ref "T1") (pin "7") (pinfunction "D_7") (pintype "passive"))
      (node (ref "T1") (pin "8") (pinfunction "D_8") (pintype "passive"))
      (node (ref "U65") (pin "1") (pinfunction "VIN_1") (pintype "power_in"))
    )
    (net (code "166") (name "/~{PWREN}") (class "Default")
      (node (ref "U66") (pin "14") (pinfunction "CBUS3_14") (pintype "bidirectional"))
    )
    (net (code "167") (name "/~{RXLED}") (class "Default")
      (node (ref "R6") (pin "1") (pinfunction "1_1") (pintype "passive"))
      (node (ref "U66") (pin "22") (pinfunction "CBUS1_22") (pintype "bidirectional"))
    )
    (net (code "168") (name "/~{SLEEP}") (class "Default")
      (node (ref "U66") (pin "12") (pinfunction "CBUS4_12") (pintype "bidirectional"))
    )
    (net (code "169") (name "/~{TXLED}") (class "Default")
      (node (ref "R5") (pin "1") (pinfunction "1_1") (pintype "passive"))
      (node (ref "U66") (pin "23") (pinfunction "CBUS0_23") (pintype "bidirectional"))
    )
    (net (code "170") (name "GND") (class "Default")
      (node (ref "C10") (pin "2") (pinfunction "2_2") (pintype "passive"))
      (node (ref "C11") (pin "2") (pinfunction "2_2") (pintype "passive"))
      (node (ref "C12") (pin "2") (pinfunction "2_2") (pintype "passive"))
      (node (ref "C13") (pin "2") (pinfunction "2_2") (pintype "passive"))
      (node (ref "C133") (pin "-") (pinfunction "-_-") (pintype "passive"))
      (node (ref "C134") (pin "-") (pinfunction "-_-") (pintype "passive"))
      (node (ref "C135") (pin "-") (pinfunction "-_-") (pintype "passive"))
      (node (ref "C136") (pin "2") (pinfunction "2_2") (pintype "passive"))
      (node (ref "C137") (pin "2") (pinfunction "2_2") (pintype "passive"))
      (node (ref "C138") (pin "2") (pinfunction "2_2") (pintype "passive"))
      (node (ref "C139") (pin "2") (pinfunction "2_2") (pintype "passive"))
      (node (ref "C14") (pin "2") (pinfunction "2_2") (pintype "passive"))
      (node (ref "C140") (pin "2") (pinfunction "2_2") (pintype "passive"))
      (node (ref "C141") (pin "-") (pinfunction "-_-") (pintype "passive"))
      (node (ref "C15") (pin "2") (pinfunction "2_2") (pintype "passive"))
      (node (ref "C16") (pin "2") (pinfunction "2_2") (pintype "passive"))
      (node (ref "C17") (pin "2") (pinfunction "2_2") (pintype "passive"))
      (node (ref "C18") (pin "2") (pinfunction "2_2") (pintype "passive"))
      (node (ref "C19") (pin "2") (pinfunction "2_2") (pintype "passive"))
      (node (ref "C2") (pin "2") (pinfunction "2_2") (pintype "passive"))
      (node (ref "C20") (pin "2") (pinfunction "2_2") (pintype "passive"))
      (node (ref "C21") (pin "2") (pinfunction "2_2") (pintype "passive"))
      (node (ref "C22") (pin "2") (pinfunction "2_2") (pintype "passive"))
      (node (ref "C23") (pin "2") (pinfunction "2_2") (pintype "passive"))
      (node (ref "C24") (pin "2") (pinfunction "2_2") (pintype "passive"))
      (node (ref "C25") (pin "2") (pinfunction "2_2") (pintype "passive"))
      (node (ref "C26") (pin "2") (pinfunction "2_2") (pintype "passive"))
      (node (ref "C27") (pin "2") (pinfunction "2_2") (pintype "passive"))
      (node (ref "C28") (pin "2") (pinfunction "2_2") (pintype "passive"))
      (node (ref "C29") (pin "2") (pinfunction "2_2") (pintype "passive"))
      (node (ref "C3") (pin "2") (pinfunction "2_2") (pintype "passive"))
      (node (ref "C30") (pin "2") (pinfunction "2_2") (pintype "passive"))
      (node (ref "C31") (pin "2") (pinfunction "2_2") (pintype "passive"))
      (node (ref "C32") (pin "2") (pinfunction "2_2") (pintype "passive"))
      (node (ref "C33") (pin "2") (pinfunction "2_2") (pintype "passive"))
      (node (ref "C34") (pin "2") (pinfunction "2_2") (pintype "passive"))
      (node (ref "C35") (pin "2") (pinfunction "2_2") (pintype "passive"))
      (node (ref "C36") (pin "2") (pinfunction "2_2") (pintype "passive"))
      (node (ref "C37") (pin "2") (pinfunction "2_2") (pintype "passive"))
      (node (ref "C38") (pin "2") (pinfunction "2_2") (pintype "passive"))
      (node (ref "C39") (pin "2") (pinfunction "2_2") (pintype "passive"))
      (node (ref "C4") (pin "2") (pinfunction "2_2") (pintype "passive"))
      (node (ref "C40") (pin "2") (pinfunction "2_2") (pintype "passive"))
      (node (ref "C41") (pin "2") (pinfunction "2_2") (pintype "passive"))
      (node (ref "C42") (pin "2") (pinfunction "2_2") (pintype "passive"))
      (node (ref "C43") (pin "2") (pinfunction "2_2") (pintype "passive"))
      (node (ref "C44") (pin "2") (pinfunction "2_2") (pintype "passive"))
      (node (ref "C45") (pin "2") (pinfunction "2_2") (pintype "passive"))
      (node (ref "C46") (pin "2") (pinfunction "2_2") (pintype "passive"))
      (node (ref "C47") (pin "2") (pinfunction "2_2") (pintype "passive"))
      (node (ref "C48") (pin "2") (pinfunction "2_2") (pintype "passive"))
      (node (ref "C49") (pin "2") (pinfunction "2_2") (pintype "passive"))
      (node (ref "C5") (pin "2") (pinfunction "2_2") (pintype "passive"))
      (node (ref "C50") (pin "2") (pinfunction "2_2") (pintype "passive"))
      (node (ref "C51") (pin "2") (pinfunction "2_2") (pintype "passive"))
      (node (ref "C52") (pin "2") (pinfunction "2_2") (pintype "passive"))
      (node (ref "C53") (pin "2") (pinfunction "2_2") (pintype "passive"))
      (node (ref "C54") (pin "2") (pinfunction "2_2") (pintype "passive"))
      (node (ref "C55") (pin "2") (pinfunction "2_2") (pintype "passive"))
      (node (ref "C56") (pin "2") (pinfunction "2_2") (pintype "passive"))
      (node (ref "C57") (pin "2") (pinfunction "2_2") (pintype "passive"))
      (node (ref "C58") (pin "2") (pinfunction "2_2") (pintype "passive"))
      (node (ref "C59") (pin "2") (pinfunction "2_2") (pintype "passive"))
      (node (ref "C6") (pin "2") (pinfunction "2_2") (pintype "passive"))
      (node (ref "C60") (pin "2") (pinfunction "2_2") (pintype "passive"))
      (node (ref "C61") (pin "2") (pinfunction "2_2") (pintype "passive"))
      (node (ref "C62") (pin "2") (pinfunction "2_2") (pintype "passive"))
      (node (ref "C63") (pin "2") (pinfunction "2_2") (pintype "passive"))
      (node (ref "C64") (pin "2") (pinfunction "2_2") (pintype "passive"))
      (node (ref "C65") (pin "2") (pinfunction "2_2") (pintype "passive"))
      (node (ref "C66") (pin "2") (pinfunction "2_2") (pintype "passive"))
      (node (ref "C67") (pin "2") (pinfunction "2_2") (pintype "passive"))
      (node (ref "C7") (pin "2") (pinfunction "2_2") (pintype "passive"))
      (node (ref "C8") (pin "2") (pinfunction "2_2") (pintype "passive"))
      (node (ref "C9") (pin "2") (pinfunction "2_2") (pintype "passive"))
      (node (ref "J1") (pin "2") (pinfunction "2_2") (pintype "passive"))
      (node (ref "J1") (pin "3") (pinfunction "3_3") (pintype "passive"))
      (node (ref "JP1") (pin "11") (pinfunction "11_11") (pintype "passive"))
      (node (ref "JP1") (pin "29") (pinfunction "29_29") (pintype "passive"))
      (node (ref "JP2") (pin "11") (pinfunction "11_11") (pintype "passive"))
      (node (ref "JP2") (pin "29") (pinfunction "29_29") (pintype "passive"))
      (node (ref "JUMPER") (pin "1") (pinfunction "1_1") (pintype "passive"))
      (node (ref "R4") (pin "1") (pinfunction "1_1") (pintype "passive"))
      (node (ref "R7") (pin "2") (pinfunction "2_2") (pintype "passive"))
      (node (ref "SV1") (pin "10") (pinfunction "10_10") (pintype "passive"))
      (node (ref "SV1") (pin "12") (pinfunction "12_12") (pintype "passive"))
      (node (ref "SV1") (pin "14") (pinfunction "14_14") (pintype "passive"))
      (node (ref "SV1") (pin "16") (pinfunction "16_16") (pintype "passive"))
      (node (ref "SV1") (pin "18") (pinfunction "18_18") (pintype "passive"))
      (node (ref "SV1") (pin "2") (pinfunction "2_2") (pintype "passive"))
      (node (ref "SV1") (pin "20") (pinfunction "20_20") (pintype "passive"))
      (node (ref "SV1") (pin "22") (pinfunction "22_22") (pintype "passive"))
      (node (ref "SV1") (pin "24") (pinfunction "24_24") (pintype "passive"))
      (node (ref "SV1") (pin "26") (pinfunction "26_26") (pintype "passive"))
      (node (ref "SV1") (pin "28") (pinfunction "28_28") (pintype "passive"))
      (node (ref "SV1") (pin "30") (pinfunction "30_30") (pintype "passive"))
      (node (ref "SV1") (pin "32") (pinfunction "32_32") (pintype "passive"))
      (node (ref "SV1") (pin "4") (pinfunction "4_4") (pintype "passive"))
      (node (ref "SV1") (pin "6") (pinfunction "6_6") (pintype "passive"))
      (node (ref "SV1") (pin "8") (pinfunction "8_8") (pintype "passive"))
      (node (ref "SV2") (pin "10") (pinfunction "10_10") (pintype "passive"))
      (node (ref "SV2") (pin "12") (pinfunction "12_12") (pintype "passive"))
      (node (ref "SV2") (pin "14") (pinfunction "14_14") (pintype "passive"))
      (node (ref "SV2") (pin "16") (pinfunction "16_16") (pintype "passive"))
      (node (ref "SV2") (pin "18") (pinfunction "18_18") (pintype "passive"))
      (node (ref "SV2") (pin "2") (pinfunction "2_2") (pintype "passive"))
      (node (ref "SV2") (pin "20") (pinfunction "20_20") (pintype "passive"))
      (node (ref "SV2") (pin "22") (pinfunction "22_22") (pintype "passive"))
      (node (ref "SV2") (pin "24") (pinfunction "24_24") (pintype "passive"))
      (node (ref "SV2") (pin "26") (pinfunction "26_26") (pintype "passive"))
      (node (ref "SV2") (pin "28") (pinfunction "28_28") (pintype "passive"))
      (node (ref "SV2") (pin "30") (pinfunction "30_30") (pintype "passive"))
      (node (ref "SV2") (pin "32") (pinfunction "32_32") (pintype "passive"))
      (node (ref "SV2") (pin "4") (pinfunction "4_4") (pintype "passive"))
      (node (ref "SV2") (pin "6") (pinfunction "6_6") (pintype "passive"))
      (node (ref "SV2") (pin "8") (pinfunction "8_8") (pintype "passive"))
      (node (ref "SV3") (pin "10") (pinfunction "10_10") (pintype "passive"))
      (node (ref "SV3") (pin "12") (pinfunction "12_12") (pintype "passive"))
      (node (ref "SV3") (pin "14") (pinfunction "14_14") (pintype "passive"))
      (node (ref "SV3") (pin "16") (pinfunction "16_16") (pintype "passive"))
      (node (ref "SV3") (pin "18") (pinfunction "18_18") (pintype "passive"))
      (node (ref "SV3") (pin "2") (pinfunction "2_2") (pintype "passive"))
      (node (ref "SV3") (pin "20") (pinfunction "20_20") (pintype "passive"))
      (node (ref "SV3") (pin "22") (pinfunction "22_22") (pintype "passive"))
      (node (ref "SV3") (pin "24") (pinfunction "24_24") (pintype "passive"))
      (node (ref "SV3") (pin "26") (pinfunction "26_26") (pintype "passive"))
      (node (ref "SV3") (pin "28") (pinfunction "28_28") (pintype "passive"))
      (node (ref "SV3") (pin "30") (pinfunction "30_30") (pintype "passive"))
      (node (ref "SV3") (pin "32") (pinfunction "32_32") (pintype "passive"))
      (node (ref "SV3") (pin "4") (pinfunction "4_4") (pintype "passive"))
      (node (ref "SV3") (pin "6") (pinfunction "6_6") (pintype "passive"))
      (node (ref "SV3") (pin "8") (pinfunction "8_8") (pintype "passive"))
      (node (ref "SV4") (pin "10") (pinfunction "10_10") (pintype "passive"))
      (node (ref "SV4") (pin "12") (pinfunction "12_12") (pintype "passive"))
      (node (ref "SV4") (pin "14") (pinfunction "14_14") (pintype "passive"))
      (node (ref "SV4") (pin "16") (pinfunction "16_16") (pintype "passive"))
      (node (ref "SV4") (pin "18") (pinfunction "18_18") (pintype "passive"))
      (node (ref "SV4") (pin "2") (pinfunction "2_2") (pintype "passive"))
      (node (ref "SV4") (pin "20") (pinfunction "20_20") (pintype "passive"))
      (node (ref "SV4") (pin "22") (pinfunction "22_22") (pintype "passive"))
      (node (ref "SV4") (pin "24") (pinfunction "24_24") (pintype "passive"))
      (node (ref "SV4") (pin "26") (pinfunction "26_26") (pintype "passive"))
      (node (ref "SV4") (pin "28") (pinfunction "28_28") (pintype "passive"))
      (node (ref "SV4") (pin "30") (pinfunction "30_30") (pintype "passive"))
      (node (ref "SV4") (pin "32") (pinfunction "32_32") (pintype "passive"))
      (node (ref "SV4") (pin "4") (pinfunction "4_4") (pintype "passive"))
      (node (ref "SV4") (pin "6") (pinfunction "6_6") (pintype "passive"))
      (node (ref "SV4") (pin "8") (pinfunction "8_8") (pintype "passive"))
      (node (ref "U1") (pin "4") (pinfunction "GND_4") (pintype "power_in"))
      (node (ref "U10") (pin "4") (pinfunction "GND_4") (pintype "power_in"))
      (node (ref "U11") (pin "4") (pinfunction "GND_4") (pintype "power_in"))
      (node (ref "U12") (pin "4") (pinfunction "GND_4") (pintype "power_in"))
      (node (ref "U13") (pin "4") (pinfunction "GND_4") (pintype "power_in"))
      (node (ref "U14") (pin "4") (pinfunction "GND_4") (pintype "power_in"))
      (node (ref "U15") (pin "4") (pinfunction "GND_4") (pintype "power_in"))
      (node (ref "U16") (pin "4") (pinfunction "GND_4") (pintype "power_in"))
      (node (ref "U17") (pin "4") (pinfunction "GND_4") (pintype "power_in"))
      (node (ref "U18") (pin "4") (pinfunction "GND_4") (pintype "power_in"))
      (node (ref "U19") (pin "4") (pinfunction "GND_4") (pintype "power_in"))
      (node (ref "U2") (pin "4") (pinfunction "GND_4") (pintype "power_in"))
      (node (ref "U20") (pin "4") (pinfunction "GND_4") (pintype "power_in"))
      (node (ref "U21") (pin "4") (pinfunction "GND_4") (pintype "power_in"))
      (node (ref "U22") (pin "4") (pinfunction "GND_4") (pintype "power_in"))
      (node (ref "U23") (pin "4") (pinfunction "GND_4") (pintype "power_in"))
      (node (ref "U24") (pin "4") (pinfunction "GND_4") (pintype "power_in"))
      (node (ref "U25") (pin "4") (pinfunction "GND_4") (pintype "power_in"))
      (node (ref "U26") (pin "4") (pinfunction "GND_4") (pintype "power_in"))
      (node (ref "U27") (pin "4") (pinfunction "GND_4") (pintype "power_in"))
      (node (ref "U28") (pin "4") (pinfunction "GND_4") (pintype "power_in"))
      (node (ref "U29") (pin "4") (pinfunction "GND_4") (pintype "power_in"))
      (node (ref "U3") (pin "4") (pinfunction "GND_4") (pintype "power_in"))
      (node (ref "U30") (pin "4") (pinfunction "GND_4") (pintype "power_in"))
      (node (ref "U31") (pin "4") (pinfunction "GND_4") (pintype "power_in"))
      (node (ref "U32") (pin "4") (pinfunction "GND_4") (pintype "power_in"))
      (node (ref "U33") (pin "4") (pinfunction "GND_4") (pintype "power_in"))
      (node (ref "U34") (pin "4") (pinfunction "GND_4") (pintype "power_in"))
      (node (ref "U35") (pin "4") (pinfunction "GND_4") (pintype "power_in"))
      (node (ref "U36") (pin "4") (pinfunction "GND_4") (pintype "power_in"))
      (node (ref "U37") (pin "4") (pinfunction "GND_4") (pintype "power_in"))
      (node (ref "U38") (pin "4") (pinfunction "GND_4") (pintype "power_in"))
      (node (ref "U39") (pin "4") (pinfunction "GND_4") (pintype "power_in"))
      (node (ref "U4") (pin "4") (pinfunction "GND_4") (pintype "power_in"))
      (node (ref "U40") (pin "4") (pinfunction "GND_4") (pintype "power_in"))
      (node (ref "U41") (pin "4") (pinfunction "GND_4") (pintype "power_in"))
      (node (ref "U42") (pin "4") (pinfunction "GND_4") (pintype "power_in"))
      (node (ref "U43") (pin "4") (pinfunction "GND_4") (pintype "power_in"))
      (node (ref "U44") (pin "4") (pinfunction "GND_4") (pintype "power_in"))
      (node (ref "U45") (pin "4") (pinfunction "GND_4") (pintype "power_in"))
      (node (ref "U46") (pin "4") (pinfunction "GND_4") (pintype "power_in"))
      (node (ref "U47") (pin "4") (pinfunction "GND_4") (pintype "power_in"))
      (node (ref "U48") (pin "4") (pinfunction "GND_4") (pintype "power_in"))
      (node (ref "U49") (pin "4") (pinfunction "GND_4") (pintype "power_in"))
      (node (ref "U5") (pin "4") (pinfunction "GND_4") (pintype "power_in"))
      (node (ref "U50") (pin "4") (pinfunction "GND_4") (pintype "power_in"))
      (node (ref "U51") (pin "4") (pinfunction "GND_4") (pintype "power_in"))
      (node (ref "U52") (pin "4") (pinfunction "GND_4") (pintype "power_in"))
      (node (ref "U53") (pin "4") (pinfunction "GND_4") (pintype "power_in"))
      (node (ref "U54") (pin "4") (pinfunction "GND_4") (pintype "power_in"))
      (node (ref "U55") (pin "4") (pinfunction "GND_4") (pintype "power_in"))
      (node (ref "U56") (pin "4") (pinfunction "GND_4") (pintype "power_in"))
      (node (ref "U57") (pin "4") (pinfunction "GND_4") (pintype "power_in"))
      (node (ref "U58") (pin "4") (pinfunction "GND_4") (pintype "power_in"))
      (node (ref "U59") (pin "4") (pinfunction "GND_4") (pintype "power_in"))
      (node (ref "U6") (pin "4") (pinfunction "GND_4") (pintype "power_in"))
      (node (ref "U60") (pin "4") (pinfunction "GND_4") (pintype "power_in"))
      (node (ref "U61") (pin "4") (pinfunction "GND_4") (pintype "power_in"))
      (node (ref "U62") (pin "4") (pinfunction "GND_4") (pintype "power_in"))
      (node (ref "U63") (pin "4") (pinfunction "GND_4") (pintype "power_in"))
      (node (ref "U64") (pin "4") (pinfunction "GND_4") (pintype "power_in"))
      (node (ref "U65") (pin "4") (pinfunction "GND_4") (pintype "power_in"))
      (node (ref "U66") (pin "18") (pinfunction "GND_18") (pintype "power_in"))
      (node (ref "U66") (pin "21") (pinfunction "GND_21") (pintype "power_in"))
      (node (ref "U66") (pin "25") (pinfunction "AGND_25") (pintype "power_in"))
      (node (ref "U66") (pin "26") (pinfunction "TEST_26") (pintype "bidirectional"))
      (node (ref "U66") (pin "7") (pinfunction "GND_7") (pintype "power_in"))
      (node (ref "U7") (pin "4") (pinfunction "GND_4") (pintype "power_in"))
      (node (ref "U8") (pin "4") (pinfunction "GND_4") (pintype "power_in"))
      (node (ref "U9") (pin "4") (pinfunction "GND_4") (pintype "power_in"))
      (node (ref "X1") (pin "5") (pinfunction "5_5") (pintype "passive"))
      (node (ref "X2") (pin "2") (pinfunction "2_2") (pintype "passive"))
    )
    (net (code "171") (name "Net-(JP1-Pad12)") (class "Default")
      (node (ref "JP1") (pin "12") (pinfunction "12_12") (pintype "passive"))
      (node (ref "R8") (pin "2") (pinfunction "2_2") (pintype "passive"))
    )
    (net (code "172") (name "Net-(L1-2)") (class "Default")
      (node (ref "D1") (pin "A") (pinfunction "A_A") (pintype "passive"))
      (node (ref "L1") (pin "C") (pinfunction "2_C") (pintype "passive"))
    )
    (net (code "173") (name "Net-(L2-1)") (class "Default")
      (node (ref "D1") (pin "C") (pinfunction "C_C") (pintype "passive"))
      (node (ref "L2") (pin "A") (pinfunction "1_A") (pintype "passive"))
    )
    (net (code "174") (name "Net-(LED1-PadC)") (class "Default")
      (node (ref "LED1") (pin "C") (pinfunction "C_C") (pintype "passive"))
      (node (ref "R5") (pin "2") (pinfunction "2_2") (pintype "passive"))
    )
    (net (code "175") (name "Net-(LED2-PadC)") (class "Default")
      (node (ref "LED2") (pin "C") (pinfunction "C_C") (pintype "passive"))
      (node (ref "R6") (pin "2") (pinfunction "2_2") (pintype "passive"))
    )
    (net (code "176") (name "Net-(T1A-G)") (class "Default")
      (node (ref "T1") (pin "2") (pinfunction "G_2") (pintype "passive"))
      (node (ref "T1") (pin "4") (pinfunction "G_4") (pintype "passive"))
      (node (ref "U65") (pin "8") (pinfunction "GATE_8") (pintype "output"))
    )
    (net (code "177") (name "Net-(T1A-S)") (class "Default")
      (node (ref "T1") (pin "1") (pinfunction "S_1") (pintype "passive"))
      (node (ref "T1") (pin "3") (pinfunction "S_3") (pintype "passive"))
    )
    (net (code "178") (name "Net-(U1-OUTH)") (class "Default")
      (node (ref "C68") (pin "1") (pinfunction "1_1") (pintype "passive"))
      (node (ref "U1") (pin "5") (pinfunction "OUTL_5") (pintype "power_in"))
      (node (ref "U1") (pin "6") (pinfunction "OUTH_6") (pintype "power_in"))
    )
    (net (code "179") (name "Net-(U2-OUTH)") (class "Default")
      (node (ref "C69") (pin "1") (pinfunction "1_1") (pintype "passive"))
      (node (ref "U2") (pin "5") (pinfunction "OUTL_5") (pintype "power_in"))
      (node (ref "U2") (pin "6") (pinfunction "OUTH_6") (pintype "power_in"))
    )
    (net (code "180") (name "Net-(U3-OUTH)") (class "Default")
      (node (ref "C70") (pin "1") (pinfunction "1_1") (pintype "passive"))
      (node (ref "U3") (pin "5") (pinfunction "OUTL_5") (pintype "power_in"))
      (node (ref "U3") (pin "6") (pinfunction "OUTH_6") (pintype "power_in"))
    )
    (net (code "181") (name "Net-(U4-OUTH)") (class "Default")
      (node (ref "C71") (pin "1") (pinfunction "1_1") (pintype "passive"))
      (node (ref "U4") (pin "5") (pinfunction "OUTL_5") (pintype "power_in"))
      (node (ref "U4") (pin "6") (pinfunction "OUTH_6") (pintype "power_in"))
    )
    (net (code "182") (name "Net-(U5-OUTH)") (class "Default")
      (node (ref "C72") (pin "1") (pinfunction "1_1") (pintype "passive"))
      (node (ref "U5") (pin "5") (pinfunction "OUTL_5") (pintype "power_in"))
      (node (ref "U5") (pin "6") (pinfunction "OUTH_6") (pintype "power_in"))
    )
    (net (code "183") (name "Net-(U6-OUTH)") (class "Default")
      (node (ref "C73") (pin "1") (pinfunction "1_1") (pintype "passive"))
      (node (ref "U6") (pin "5") (pinfunction "OUTL_5") (pintype "power_in"))
      (node (ref "U6") (pin "6") (pinfunction "OUTH_6") (pintype "power_in"))
    )
    (net (code "184") (name "Net-(U7-OUTH)") (class "Default")
      (node (ref "C74") (pin "1") (pinfunction "1_1") (pintype "passive"))
      (node (ref "U7") (pin "5") (pinfunction "OUTL_5") (pintype "power_in"))
      (node (ref "U7") (pin "6") (pinfunction "OUTH_6") (pintype "power_in"))
    )
    (net (code "185") (name "Net-(U8-OUTH)") (class "Default")
      (node (ref "C75") (pin "1") (pinfunction "1_1") (pintype "passive"))
      (node (ref "U8") (pin "5") (pinfunction "OUTL_5") (pintype "power_in"))
      (node (ref "U8") (pin "6") (pinfunction "OUTH_6") (pintype "power_in"))
    )
    (net (code "186") (name "Net-(U9-OUTH)") (class "Default")
      (node (ref "C76") (pin "1") (pinfunction "1_1") (pintype "passive"))
      (node (ref "U9") (pin "5") (pinfunction "OUTL_5") (pintype "power_in"))
      (node (ref "U9") (pin "6") (pinfunction "OUTH_6") (pintype "power_in"))
    )
    (net (code "187") (name "Net-(U10-OUTH)") (class "Default")
      (node (ref "C77") (pin "1") (pinfunction "1_1") (pintype "passive"))
      (node (ref "U10") (pin "5") (pinfunction "OUTL_5") (pintype "power_in"))
      (node (ref "U10") (pin "6") (pinfunction "OUTH_6") (pintype "power_in"))
    )
    (net (code "188") (name "Net-(U11-OUTH)") (class "Default")
      (node (ref "C78") (pin "1") (pinfunction "1_1") (pintype "passive"))
      (node (ref "U11") (pin "5") (pinfunction "OUTL_5") (pintype "power_in"))
      (node (ref "U11") (pin "6") (pinfunction "OUTH_6") (pintype "power_in"))
    )
    (net (code "189") (name "Net-(U12-OUTH)") (class "Default")
      (node (ref "C79") (pin "1") (pinfunction "1_1") (pintype "passive"))
      (node (ref "U12") (pin "5") (pinfunction "OUTL_5") (pintype "power_in"))
      (node (ref "U12") (pin "6") (pinfunction "OUTH_6") (pintype "power_in"))
    )
    (net (code "190") (name "Net-(U13-OUTH)") (class "Default")
      (node (ref "C80") (pin "1") (pinfunction "1_1") (pintype "passive"))
      (node (ref "U13") (pin "5") (pinfunction "OUTL_5") (pintype "power_in"))
      (node (ref "U13") (pin "6") (pinfunction "OUTH_6") (pintype "power_in"))
    )
    (net (code "191") (name "Net-(U14-OUTH)") (class "Default")
      (node (ref "C81") (pin "1") (pinfunction "1_1") (pintype "passive"))
      (node (ref "U14") (pin "5") (pinfunction "OUTL_5") (pintype "power_in"))
      (node (ref "U14") (pin "6") (pinfunction "OUTH_6") (pintype "power_in"))
    )
    (net (code "192") (name "Net-(U15-OUTH)") (class "Default")
      (node (ref "C82") (pin "1") (pinfunction "1_1") (pintype "passive"))
      (node (ref "U15") (pin "5") (pinfunction "OUTL_5") (pintype "power_in"))
      (node (ref "U15") (pin "6") (pinfunction "OUTH_6") (pintype "power_in"))
    )
    (net (code "193") (name "Net-(U16-OUTH)") (class "Default")
      (node (ref "C83") (pin "1") (pinfunction "1_1") (pintype "passive"))
      (node (ref "U16") (pin "5") (pinfunction "OUTL_5") (pintype "power_in"))
      (node (ref "U16") (pin "6") (pinfunction "OUTH_6") (pintype "power_in"))
    )
    (net (code "194") (name "Net-(U17-OUTH)") (class "Default")
      (node (ref "C84") (pin "1") (pinfunction "1_1") (pintype "passive"))
      (node (ref "U17") (pin "5") (pinfunction "OUTL_5") (pintype "power_in"))
      (node (ref "U17") (pin "6") (pinfunction "OUTH_6") (pintype "power_in"))
    )
    (net (code "195") (name "Net-(U18-OUTH)") (class "Default")
      (node (ref "C85") (pin "1") (pinfunction "1_1") (pintype "passive"))
      (node (ref "U18") (pin "5") (pinfunction "OUTL_5") (pintype "power_in"))
      (node (ref "U18") (pin "6") (pinfunction "OUTH_6") (pintype "power_in"))
    )
    (net (code "196") (name "Net-(U19-OUTH)") (class "Default")
      (node (ref "C86") (pin "1") (pinfunction "1_1") (pintype "passive"))
      (node (ref "U19") (pin "5") (pinfunction "OUTL_5") (pintype "power_in"))
      (node (ref "U19") (pin "6") (pinfunction "OUTH_6") (pintype "power_in"))
    )
    (net (code "197") (name "Net-(U20-OUTH)") (class "Default")
      (node (ref "C87") (pin "1") (pinfunction "1_1") (pintype "passive"))
      (node (ref "U20") (pin "5") (pinfunction "OUTL_5") (pintype "power_in"))
      (node (ref "U20") (pin "6") (pinfunction "OUTH_6") (pintype "power_in"))
    )
    (net (code "198") (name "Net-(U21-OUTH)") (class "Default")
      (node (ref "C88") (pin "1") (pinfunction "1_1") (pintype "passive"))
      (node (ref "U21") (pin "5") (pinfunction "OUTL_5") (pintype "power_in"))
      (node (ref "U21") (pin "6") (pinfunction "OUTH_6") (pintype "power_in"))
    )
    (net (code "199") (name "Net-(U22-OUTH)") (class "Default")
      (node (ref "C89") (pin "1") (pinfunction "1_1") (pintype "passive"))
      (node (ref "U22") (pin "5") (pinfunction "OUTL_5") (pintype "power_in"))
      (node (ref "U22") (pin "6") (pinfunction "OUTH_6") (pintype "power_in"))
    )
    (net (code "200") (name "Net-(U23-OUTH)") (class "Default")
      (node (ref "C90") (pin "1") (pinfunction "1_1") (pintype "passive"))
      (node (ref "U23") (pin "5") (pinfunction "OUTL_5") (pintype "power_in"))
      (node (ref "U23") (pin "6") (pinfunction "OUTH_6") (pintype "power_in"))
    )
    (net (code "201") (name "Net-(U24-OUTH)") (class "Default")
      (node (ref "C91") (pin "1") (pinfunction "1_1") (pintype "passive"))
      (node (ref "U24") (pin "5") (pinfunction "OUTL_5") (pintype "power_in"))
      (node (ref "U24") (pin "6") (pinfunction "OUTH_6") (pintype "power_in"))
    )
    (net (code "202") (name "Net-(U25-OUTH)") (class "Default")
      (node (ref "C92") (pin "1") (pinfunction "1_1") (pintype "passive"))
      (node (ref "U25") (pin "5") (pinfunction "OUTL_5") (pintype "power_in"))
      (node (ref "U25") (pin "6") (pinfunction "OUTH_6") (pintype "power_in"))
    )
    (net (code "203") (name "Net-(U26-OUTH)") (class "Default")
      (node (ref "C93") (pin "1") (pinfunction "1_1") (pintype "passive"))
      (node (ref "U26") (pin "5") (pinfunction "OUTL_5") (pintype "power_in"))
      (node (ref "U26") (pin "6") (pinfunction "OUTH_6") (pintype "power_in"))
    )
    (net (code "204") (name "Net-(U27-OUTH)") (class "Default")
      (node (ref "C94") (pin "1") (pinfunction "1_1") (pintype "passive"))
      (node (ref "U27") (pin "5") (pinfunction "OUTL_5") (pintype "power_in"))
      (node (ref "U27") (pin "6") (pinfunction "OUTH_6") (pintype "power_in"))
    )
    (net (code "205") (name "Net-(U28-OUTH)") (class "Default")
      (node (ref "C95") (pin "1") (pinfunction "1_1") (pintype "passive"))
      (node (ref "U28") (pin "5") (pinfunction "OUTL_5") (pintype "power_in"))
      (node (ref "U28") (pin "6") (pinfunction "OUTH_6") (pintype "power_in"))
    )
    (net (code "206") (name "Net-(U29-OUTH)") (class "Default")
      (node (ref "C96") (pin "1") (pinfunction "1_1") (pintype "passive"))
      (node (ref "U29") (pin "5") (pinfunction "OUTL_5") (pintype "power_in"))
      (node (ref "U29") (pin "6") (pinfunction "OUTH_6") (pintype "power_in"))
    )
    (net (code "207") (name "Net-(U30-OUTH)") (class "Default")
      (node (ref "C97") (pin "1") (pinfunction "1_1") (pintype "passive"))
      (node (ref "U30") (pin "5") (pinfunction "OUTL_5") (pintype "power_in"))
      (node (ref "U30") (pin "6") (pinfunction "OUTH_6") (pintype "power_in"))
    )
    (net (code "208") (name "Net-(U31-OUTH)") (class "Default")
      (node (ref "C98") (pin "1") (pinfunction "1_1") (pintype "passive"))
      (node (ref "U31") (pin "5") (pinfunction "OUTL_5") (pintype "power_in"))
      (node (ref "U31") (pin "6") (pinfunction "OUTH_6") (pintype "power_in"))
    )
    (net (code "209") (name "Net-(U32-OUTH)") (class "Default")
      (node (ref "C99") (pin "1") (pinfunction "1_1") (pintype "passive"))
      (node (ref "U32") (pin "5") (pinfunction "OUTL_5") (pintype "power_in"))
      (node (ref "U32") (pin "6") (pinfunction "OUTH_6") (pintype "power_in"))
    )
    (net (code "210") (name "Net-(U33-OUTH)") (class "Default")
      (node (ref "C100") (pin "1") (pinfunction "1_1") (pintype "passive"))
      (node (ref "U33") (pin "5") (pinfunction "OUTL_5") (pintype "power_in"))
      (node (ref "U33") (pin "6") (pinfunction "OUTH_6") (pintype "power_in"))
    )
    (net (code "211") (name "Net-(U34-OUTH)") (class "Default")
      (node (ref "C101") (pin "1") (pinfunction "1_1") (pintype "passive"))
      (node (ref "U34") (pin "5") (pinfunction "OUTL_5") (pintype "power_in"))
      (node (ref "U34") (pin "6") (pinfunction "OUTH_6") (pintype "power_in"))
    )
    (net (code "212") (name "Net-(U35-OUTH)") (class "Default")
      (node (ref "C102") (pin "1") (pinfunction "1_1") (pintype "passive"))
      (node (ref "U35") (pin "5") (pinfunction "OUTL_5") (pintype "power_in"))
      (node (ref "U35") (pin "6") (pinfunction "OUTH_6") (pintype "power_in"))
    )
    (net (code "213") (name "Net-(U36-OUTH)") (class "Default")
      (node (ref "C103") (pin "1") (pinfunction "1_1") (pintype "passive"))
      (node (ref "U36") (pin "5") (pinfunction "OUTL_5") (pintype "power_in"))
      (node (ref "U36") (pin "6") (pinfunction "OUTH_6") (pintype "power_in"))
    )
    (net (code "214") (name "Net-(U37-OUTH)") (class "Default")
      (node (ref "C104") (pin "1") (pinfunction "1_1") (pintype "passive"))
      (node (ref "U37") (pin "5") (pinfunction "OUTL_5") (pintype "power_in"))
      (node (ref "U37") (pin "6") (pinfunction "OUTH_6") (pintype "power_in"))
    )
    (net (code "215") (name "Net-(U38-OUTH)") (class "Default")
      (node (ref "C105") (pin "1") (pinfunction "1_1") (pintype "passive"))
      (node (ref "U38") (pin "5") (pinfunction "OUTL_5") (pintype "power_in"))
      (node (ref "U38") (pin "6") (pinfunction "OUTH_6") (pintype "power_in"))
    )
    (net (code "216") (name "Net-(U39-OUTH)") (class "Default")
      (node (ref "C106") (pin "1") (pinfunction "1_1") (pintype "passive"))
      (node (ref "U39") (pin "5") (pinfunction "OUTL_5") (pintype "power_in"))
      (node (ref "U39") (pin "6") (pinfunction "OUTH_6") (pintype "power_in"))
    )
    (net (code "217") (name "Net-(U40-OUTH)") (class "Default")
      (node (ref "C107") (pin "1") (pinfunction "1_1") (pintype "passive"))
      (node (ref "U40") (pin "5") (pinfunction "OUTL_5") (pintype "power_in"))
      (node (ref "U40") (pin "6") (pinfunction "OUTH_6") (pintype "power_in"))
    )
    (net (code "218") (name "Net-(U41-OUTH)") (class "Default")
      (node (ref "C108") (pin "1") (pinfunction "1_1") (pintype "passive"))
      (node (ref "U41") (pin "5") (pinfunction "OUTL_5") (pintype "power_in"))
      (node (ref "U41") (pin "6") (pinfunction "OUTH_6") (pintype "power_in"))
    )
    (net (code "219") (name "Net-(U42-OUTH)") (class "Default")
      (node (ref "C109") (pin "1") (pinfunction "1_1") (pintype "passive"))
      (node (ref "U42") (pin "5") (pinfunction "OUTL_5") (pintype "power_in"))
      (node (ref "U42") (pin "6") (pinfunction "OUTH_6") (pintype "power_in"))
    )
    (net (code "220") (name "Net-(U43-OUTH)") (class "Default")
      (node (ref "C110") (pin "1") (pinfunction "1_1") (pintype "passive"))
      (node (ref "U43") (pin "5") (pinfunction "OUTL_5") (pintype "power_in"))
      (node (ref "U43") (pin "6") (pinfunction "OUTH_6") (pintype "power_in"))
    )
    (net (code "221") (name "Net-(U44-OUTH)") (class "Default")
      (node (ref "C111") (pin "1") (pinfunction "1_1") (pintype "passive"))
      (node (ref "U44") (pin "5") (pinfunction "OUTL_5") (pintype "power_in"))
      (node (ref "U44") (pin "6") (pinfunction "OUTH_6") (pintype "power_in"))
    )
    (net (code "222") (name "Net-(U45-OUTH)") (class "Default")
      (node (ref "C112") (pin "1") (pinfunction "1_1") (pintype "passive"))
      (node (ref "U45") (pin "5") (pinfunction "OUTL_5") (pintype "power_in"))
      (node (ref "U45") (pin "6") (pinfunction "OUTH_6") (pintype "power_in"))
    )
    (net (code "223") (name "Net-(U46-OUTH)") (class "Default")
      (node (ref "C113") (pin "1") (pinfunction "1_1") (pintype "passive"))
      (node (ref "U46") (pin "5") (pinfunction "OUTL_5") (pintype "power_in"))
      (node (ref "U46") (pin "6") (pinfunction "OUTH_6") (pintype "power_in"))
    )
    (net (code "224") (name "Net-(U47-OUTH)") (class "Default")
      (node (ref "C114") (pin "1") (pinfunction "1_1") (pintype "passive"))
      (node (ref "U47") (pin "5") (pinfunction "OUTL_5") (pintype "power_in"))
      (node (ref "U47") (pin "6") (pinfunction "OUTH_6") (pintype "power_in"))
    )
    (net (code "225") (name "Net-(U48-OUTH)") (class "Default")
      (node (ref "C115") (pin "1") (pinfunction "1_1") (pintype "passive"))
      (node (ref "U48") (pin "5") (pinfunction "OUTL_5") (pintype "power_in"))
      (node (ref "U48") (pin "6") (pinfunction "OUTH_6") (pintype "power_in"))
    )
    (net (code "226") (name "Net-(U49-OUTH)") (class "Default")
      (node (ref "C116") (pin "1") (pinfunction "1_1") (pintype "passive"))
      (node (ref "U49") (pin "5") (pinfunction "OUTL_5") (pintype "power_in"))
      (node (ref "U49") (pin "6") (pinfunction "OUTH_6") (pintype "power_in"))
    )
    (net (code "227") (name "Net-(U50-OUTH)") (class "Default")
      (node (ref "C117") (pin "1") (pinfunction "1_1") (pintype "passive"))
      (node (ref "U50") (pin "5") (pinfunction "OUTL_5") (pintype "power_in"))
      (node (ref "U50") (pin "6") (pinfunction "OUTH_6") (pintype "power_in"))
    )
    (net (code "228") (name "Net-(U51-OUTH)") (class "Default")
      (node (ref "C118") (pin "1") (pinfunction "1_1") (pintype "passive"))
      (node (ref "U51") (pin "5") (pinfunction "OUTL_5") (pintype "power_in"))
      (node (ref "U51") (pin "6") (pinfunction "OUTH_6") (pintype "power_in"))
    )
    (net (code "229") (name "Net-(U52-OUTH)") (class "Default")
      (node (ref "C119") (pin "1") (pinfunction "1_1") (pintype "passive"))
      (node (ref "U52") (pin "5") (pinfunction "OUTL_5") (pintype "power_in"))
      (node (ref "U52") (pin "6") (pinfunction "OUTH_6") (pintype "power_in"))
    )
    (net (code "230") (name "Net-(U53-OUTH)") (class "Default")
      (node (ref "C120") (pin "1") (pinfunction "1_1") (pintype "passive"))
      (node (ref "U53") (pin "5") (pinfunction "OUTL_5") (pintype "power_in"))
      (node (ref "U53") (pin "6") (pinfunction "OUTH_6") (pintype "power_in"))
    )
    (net (code "231") (name "Net-(U54-OUTH)") (class "Default")
      (node (ref "C121") (pin "1") (pinfunction "1_1") (pintype "passive"))
      (node (ref "U54") (pin "5") (pinfunction "OUTL_5") (pintype "power_in"))
      (node (ref "U54") (pin "6") (pinfunction "OUTH_6") (pintype "power_in"))
    )
    (net (code "232") (name "Net-(U55-OUTH)") (class "Default")
      (node (ref "C122") (pin "1") (pinfunction "1_1") (pintype "passive"))
      (node (ref "U55") (pin "5") (pinfunction "OUTL_5") (pintype "power_in"))
      (node (ref "U55") (pin "6") (pinfunction "OUTH_6") (pintype "power_in"))
    )
    (net (code "233") (name "Net-(U56-OUTH)") (class "Default")
      (node (ref "C123") (pin "1") (pinfunction "1_1") (pintype "passive"))
      (node (ref "U56") (pin "5") (pinfunction "OUTL_5") (pintype "power_in"))
      (node (ref "U56") (pin "6") (pinfunction "OUTH_6") (pintype "power_in"))
    )
    (net (code "234") (name "Net-(U57-OUTH)") (class "Default")
      (node (ref "C124") (pin "1") (pinfunction "1_1") (pintype "passive"))
      (node (ref "U57") (pin "5") (pinfunction "OUTL_5") (pintype "power_in"))
      (node (ref "U57") (pin "6") (pinfunction "OUTH_6") (pintype "power_in"))
    )
    (net (code "235") (name "Net-(U58-OUTH)") (class "Default")
      (node (ref "C125") (pin "1") (pinfunction "1_1") (pintype "passive"))
      (node (ref "U58") (pin "5") (pinfunction "OUTL_5") (pintype "power_in"))
      (node (ref "U58") (pin "6") (pinfunction "OUTH_6") (pintype "power_in"))
    )
    (net (code "236") (name "Net-(U59-OUTH)") (class "Default")
      (node (ref "C126") (pin "1") (pinfunction "1_1") (pintype "passive"))
      (node (ref "U59") (pin "5") (pinfunction "OUTL_5") (pintype "power_in"))
      (node (ref "U59") (pin "6") (pinfunction "OUTH_6") (pintype "power_in"))
    )
    (net (code "237") (name "Net-(U60-OUTH)") (class "Default")
      (node (ref "C127") (pin "1") (pinfunction "1_1") (pintype "passive"))
      (node (ref "U60") (pin "5") (pinfunction "OUTL_5") (pintype "power_in"))
      (node (ref "U60") (pin "6") (pinfunction "OUTH_6") (pintype "power_in"))
    )
    (net (code "238") (name "Net-(U61-OUTH)") (class "Default")
      (node (ref "C128") (pin "1") (pinfunction "1_1") (pintype "passive"))
      (node (ref "U61") (pin "5") (pinfunction "OUTL_5") (pintype "power_in"))
      (node (ref "U61") (pin "6") (pinfunction "OUTH_6") (pintype "power_in"))
    )
    (net (code "239") (name "Net-(U62-OUTH)") (class "Default")
      (node (ref "C129") (pin "1") (pinfunction "1_1") (pintype "passive"))
      (node (ref "U62") (pin "5") (pinfunction "OUTL_5") (pintype "power_in"))
      (node (ref "U62") (pin "6") (pinfunction "OUTH_6") (pintype "power_in"))
    )
    (net (code "240") (name "Net-(U63-OUTH)") (class "Default")
      (node (ref "C1130") (pin "1") (pinfunction "1_1") (pintype "passive"))
      (node (ref "U63") (pin "5") (pinfunction "OUTL_5") (pintype "power_in"))
      (node (ref "U63") (pin "6") (pinfunction "OUTH_6") (pintype "power_in"))
    )
    (net (code "241") (name "Net-(U64-OUTH)") (class "Default")
      (node (ref "C1131") (pin "1") (pinfunction "1_1") (pintype "passive"))
      (node (ref "U64") (pin "5") (pinfunction "OUTL_5") (pintype "power_in"))
      (node (ref "U64") (pin "6") (pinfunction "OUTH_6") (pintype "power_in"))
    )
    (net (code "242") (name "Net-(U65-OV)") (class "Default")
      (node (ref "R3") (pin "1") (pinfunction "1_1") (pintype "passive"))
      (node (ref "R4") (pin "2") (pinfunction "2_2") (pintype "passive"))
      (node (ref "U65") (pin "3") (pinfunction "OV_3") (pintype "input"))
    )
    (net (code "243") (name "Net-(U65-UV)") (class "Default")
      (node (ref "R2") (pin "1") (pinfunction "1_1") (pintype "passive"))
      (node (ref "R3") (pin "2") (pinfunction "2_2") (pintype "passive"))
      (node (ref "U65") (pin "2") (pinfunction "UV_2") (pintype "input"))
    )
    (net (code "244") (name "Net-(U65-~{SHDN})") (class "Default")
      (node (ref "R1") (pin "1") (pinfunction "1_1") (pintype "passive"))
      (node (ref "U65") (pin "5") (pinfunction "~{SHDN}_5") (pintype "input"))
    )
    (net (code "245") (name "unconnected-(JP1-Pad4)") (class "Default")
      (node (ref "JP1") (pin "4") (pinfunction "4_4") (pintype "passive"))
    )
    (net (code "246") (name "unconnected-(JP1-Pad30)") (class "Default")
      (node (ref "JP1") (pin "30") (pinfunction "30_30") (pintype "passive"))
    )
    (net (code "247") (name "unconnected-(JP1-Pad39)") (class "Default")
      (node (ref "JP1") (pin "39") (pinfunction "39_39") (pintype "passive"))
    )
    (net (code "248") (name "unconnected-(JP2-Pad4)") (class "Default")
      (node (ref "JP2") (pin "4") (pinfunction "4_4") (pintype "passive"))
    )
    (net (code "249") (name "unconnected-(JP2-Pad12)") (class "Default")
      (node (ref "JP2") (pin "12") (pinfunction "12_12") (pintype "passive"))
    )
    (net (code "250") (name "unconnected-(JP2-Pad30)") (class "Default")
      (node (ref "JP2") (pin "30") (pinfunction "30_30") (pintype "passive"))
    )
    (net (code "251") (name "unconnected-(JP2-Pad39)") (class "Default")
      (node (ref "JP2") (pin "39") (pinfunction "39_39") (pintype "passive"))
    )
    (net (code "252") (name "unconnected-(U65-~{FAULT}-Pad6)") (class "Default")
      (node (ref "U65") (pin "6") (pinfunction "~{FAULT}_6") (pintype "output"))
    )
    (net (code "253") (name "unconnected-(U66-NC-Pad8)") (class "Default")
      (node (ref "U66") (pin "8") (pinfunction "NC_8") (pintype "no_connect"))
    )
    (net (code "254") (name "unconnected-(U66-NC2-Pad24)") (class "Default")
      (node (ref "U66") (pin "24") (pinfunction "NC2_24") (pintype "no_connect"))
    )
    (net (code "255") (name "unconnected-(U66-~{CTS}-Pad11)") (class "Default")
      (node (ref "U66") (pin "11") (pinfunction "~{CTS}_11") (pintype "bidirectional"))
    )
    (net (code "256") (name "unconnected-(U66-~{DCD}-Pad10)") (class "Default")
      (node (ref "U66") (pin "10") (pinfunction "~{DCD}_10") (pintype "bidirectional"))
    )
    (net (code "257") (name "unconnected-(U66-~{DSR}-Pad9)") (class "Default")
      (node (ref "U66") (pin "9") (pinfunction "~{DSR}_9") (pintype "bidirectional"))
    )
    (net (code "258") (name "unconnected-(U66-~{DTR}-Pad2)") (class "Default")
      (node (ref "U66") (pin "2") (pinfunction "~{DTR}_2") (pintype "bidirectional"))
    )
    (net (code "259") (name "unconnected-(U66-~{RESET}-Pad19)") (class "Default")
      (node (ref "U66") (pin "19") (pinfunction "~{RESET}_19") (pintype "passive"))
    )
    (net (code "260") (name "unconnected-(U66-~{RI}-Pad6)") (class "Default")
      (node (ref "U66") (pin "6") (pinfunction "~{RI}_6") (pintype "bidirectional"))
    )
    (net (code "261") (name "unconnected-(U66-~{RTS}-Pad3)") (class "Default")
      (node (ref "U66") (pin "3") (pinfunction "~{RTS}_3") (pintype "bidirectional"))
    )
  )
)
